# Blueberry_Pi.net
KiCad netlist of a schematic drawn in EAGLE
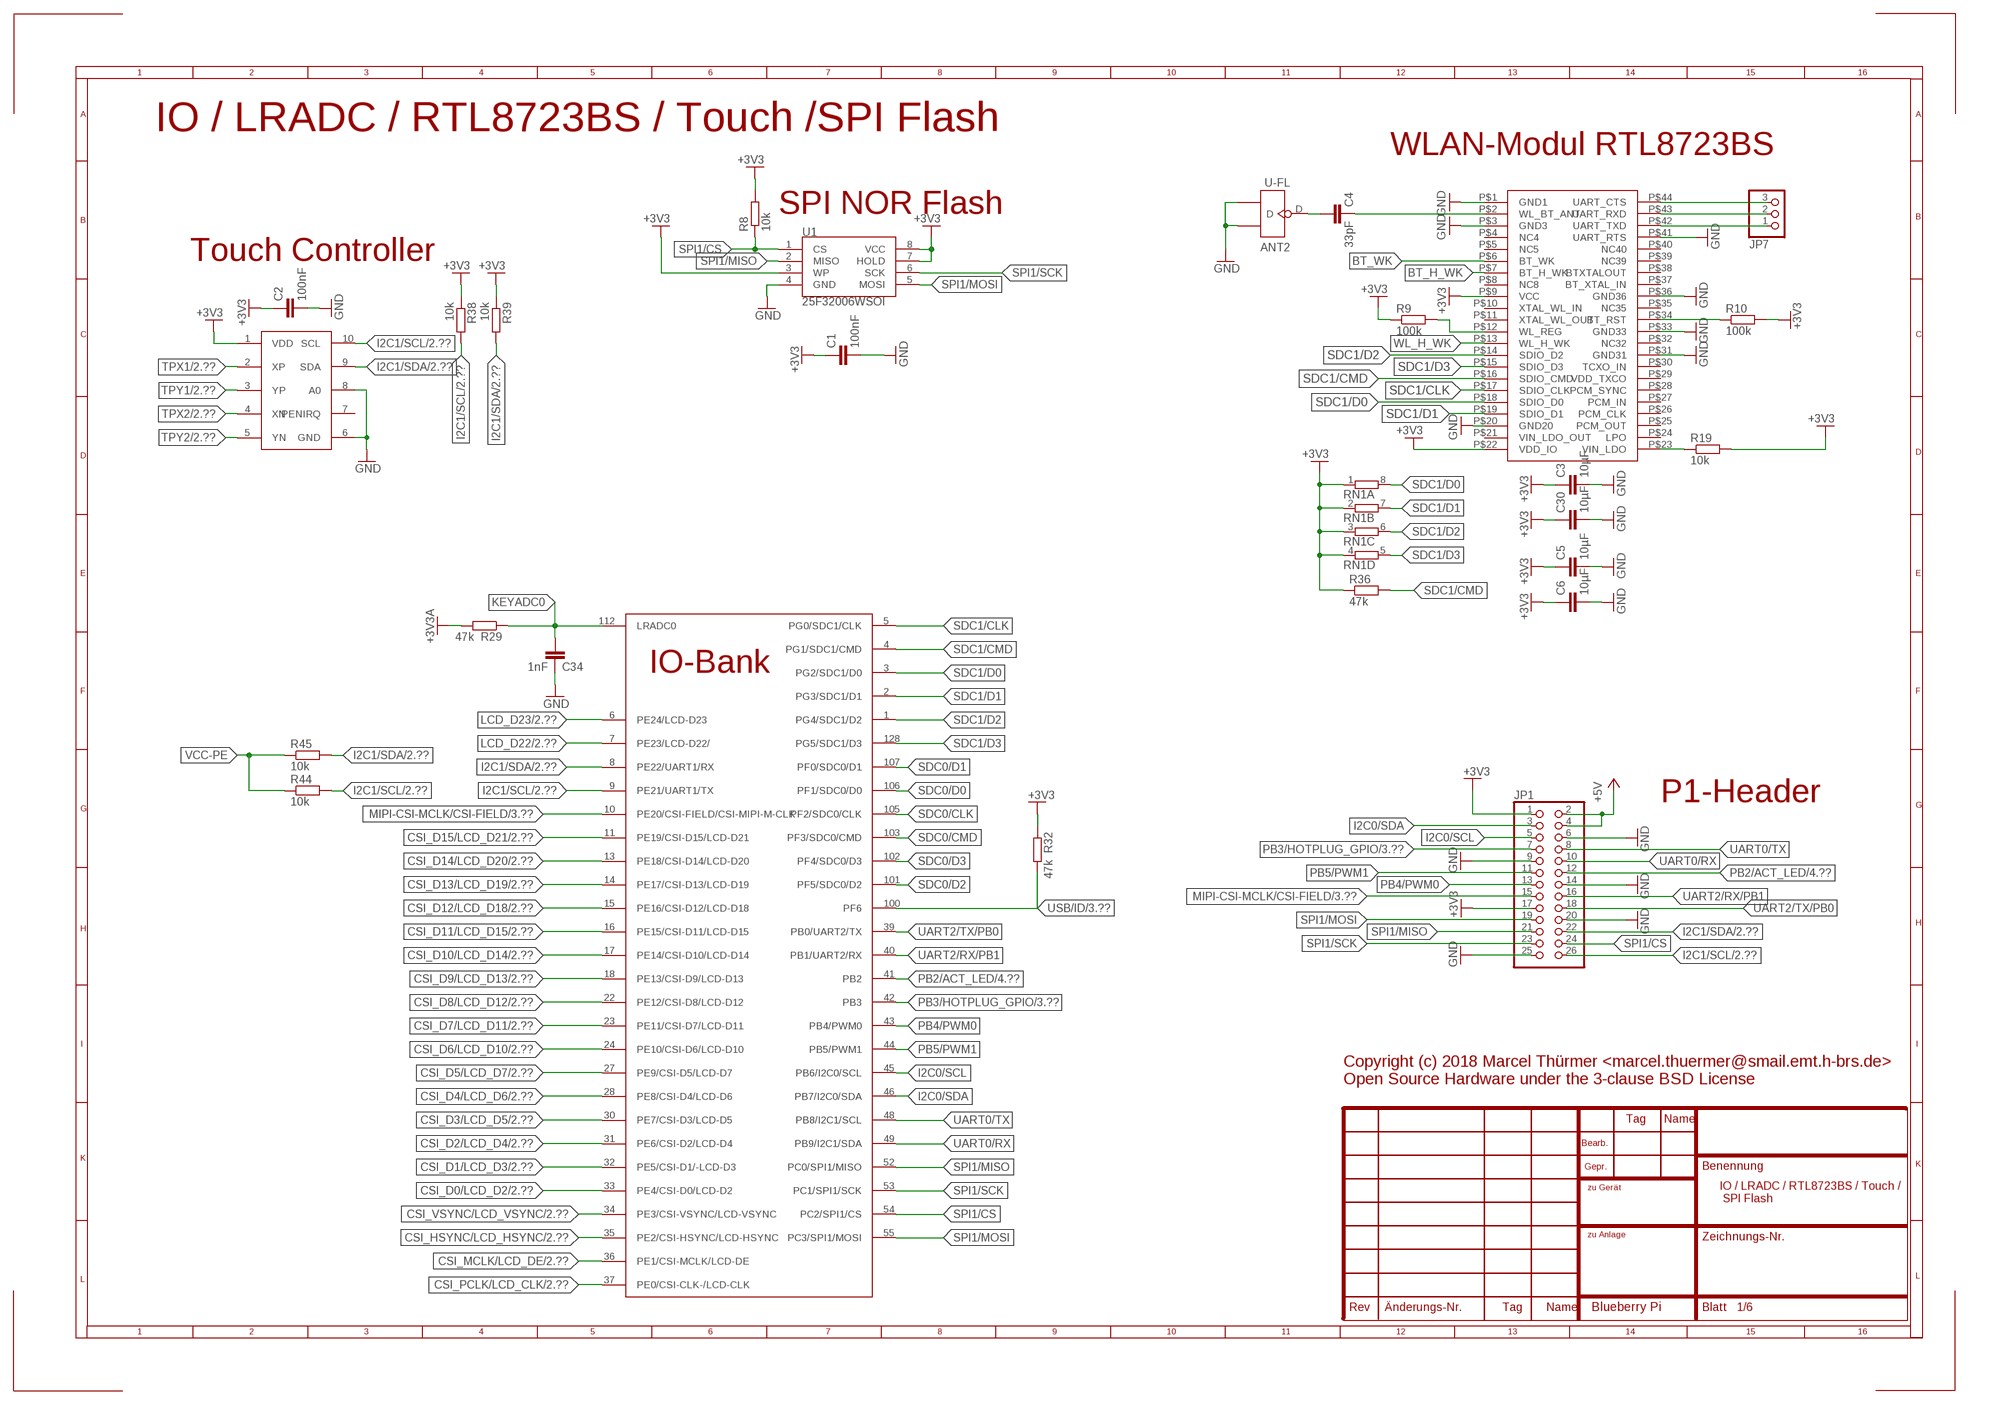
[diagram p0: schematic, sheet 1]
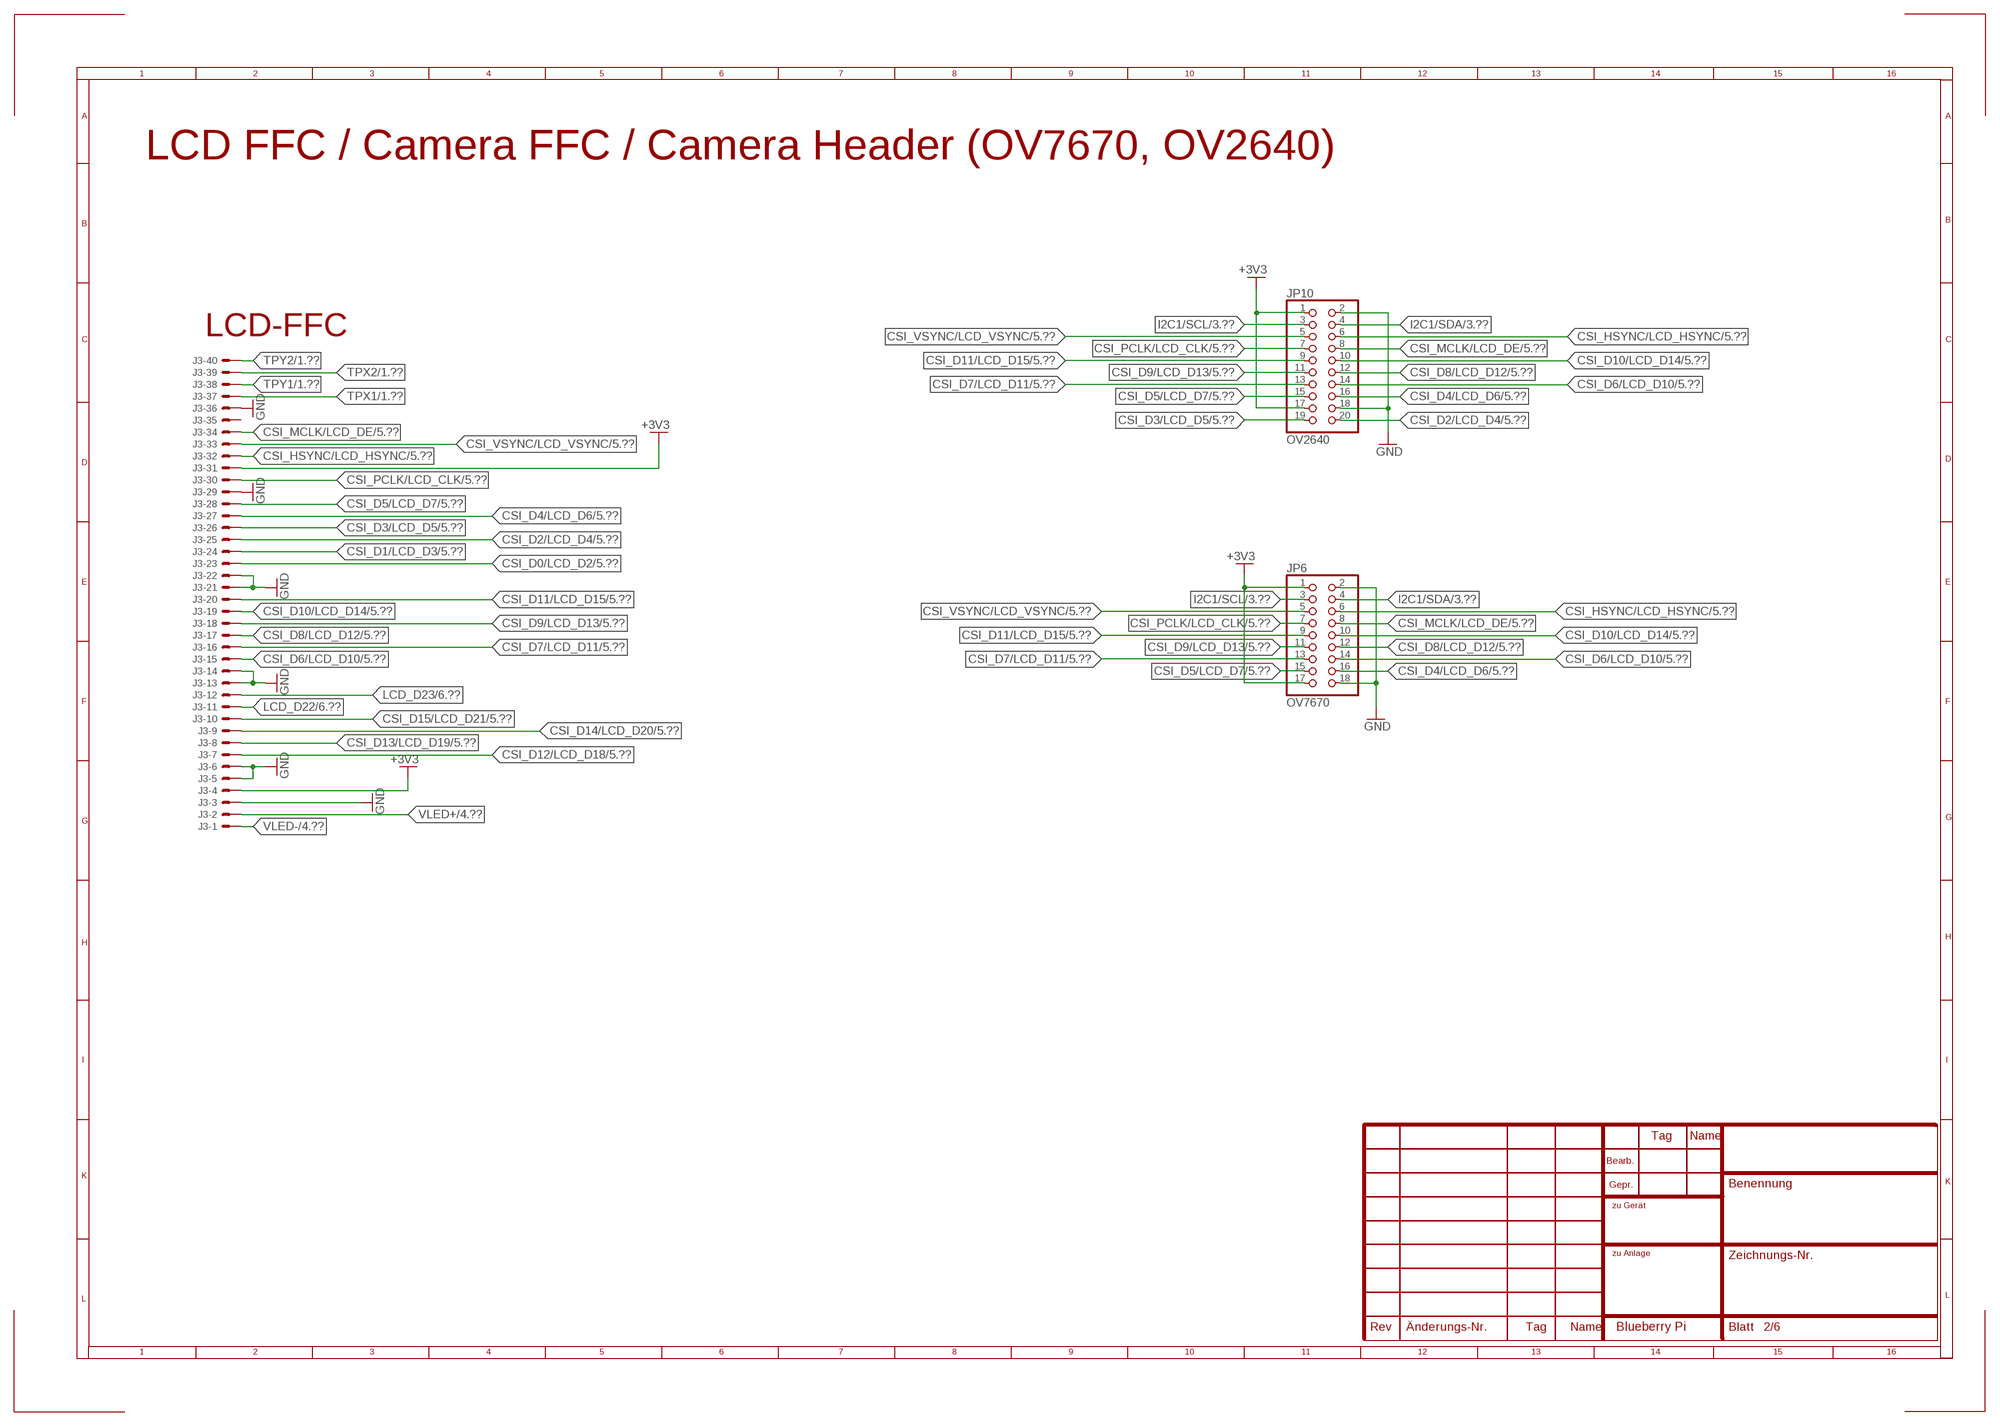
[diagram p1: schematic, sheet 2]
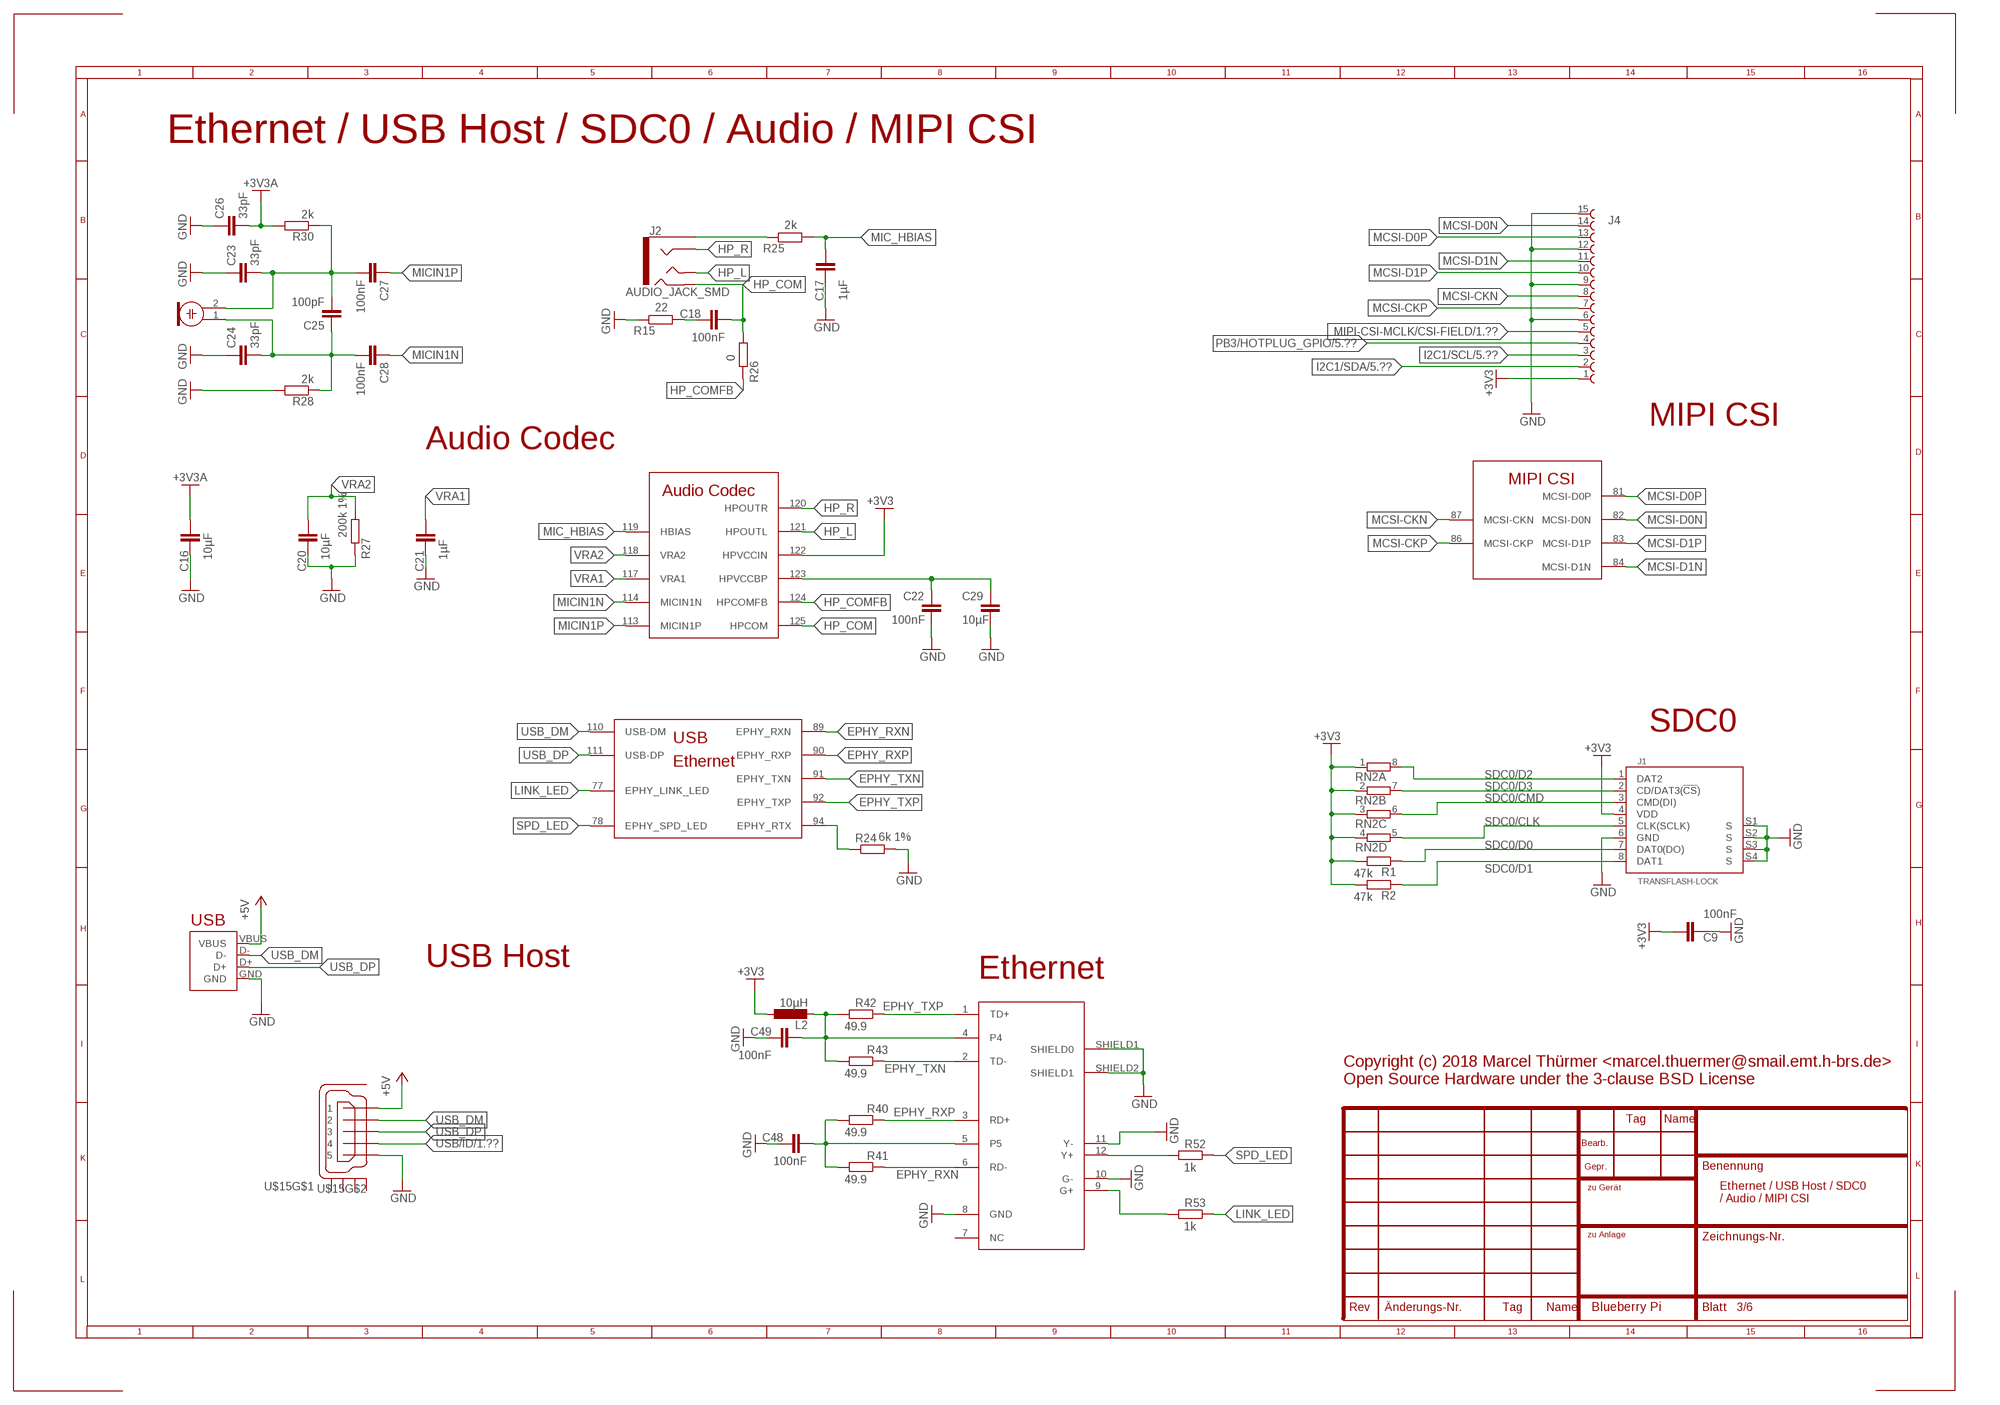
[diagram p2: schematic, sheet 3]
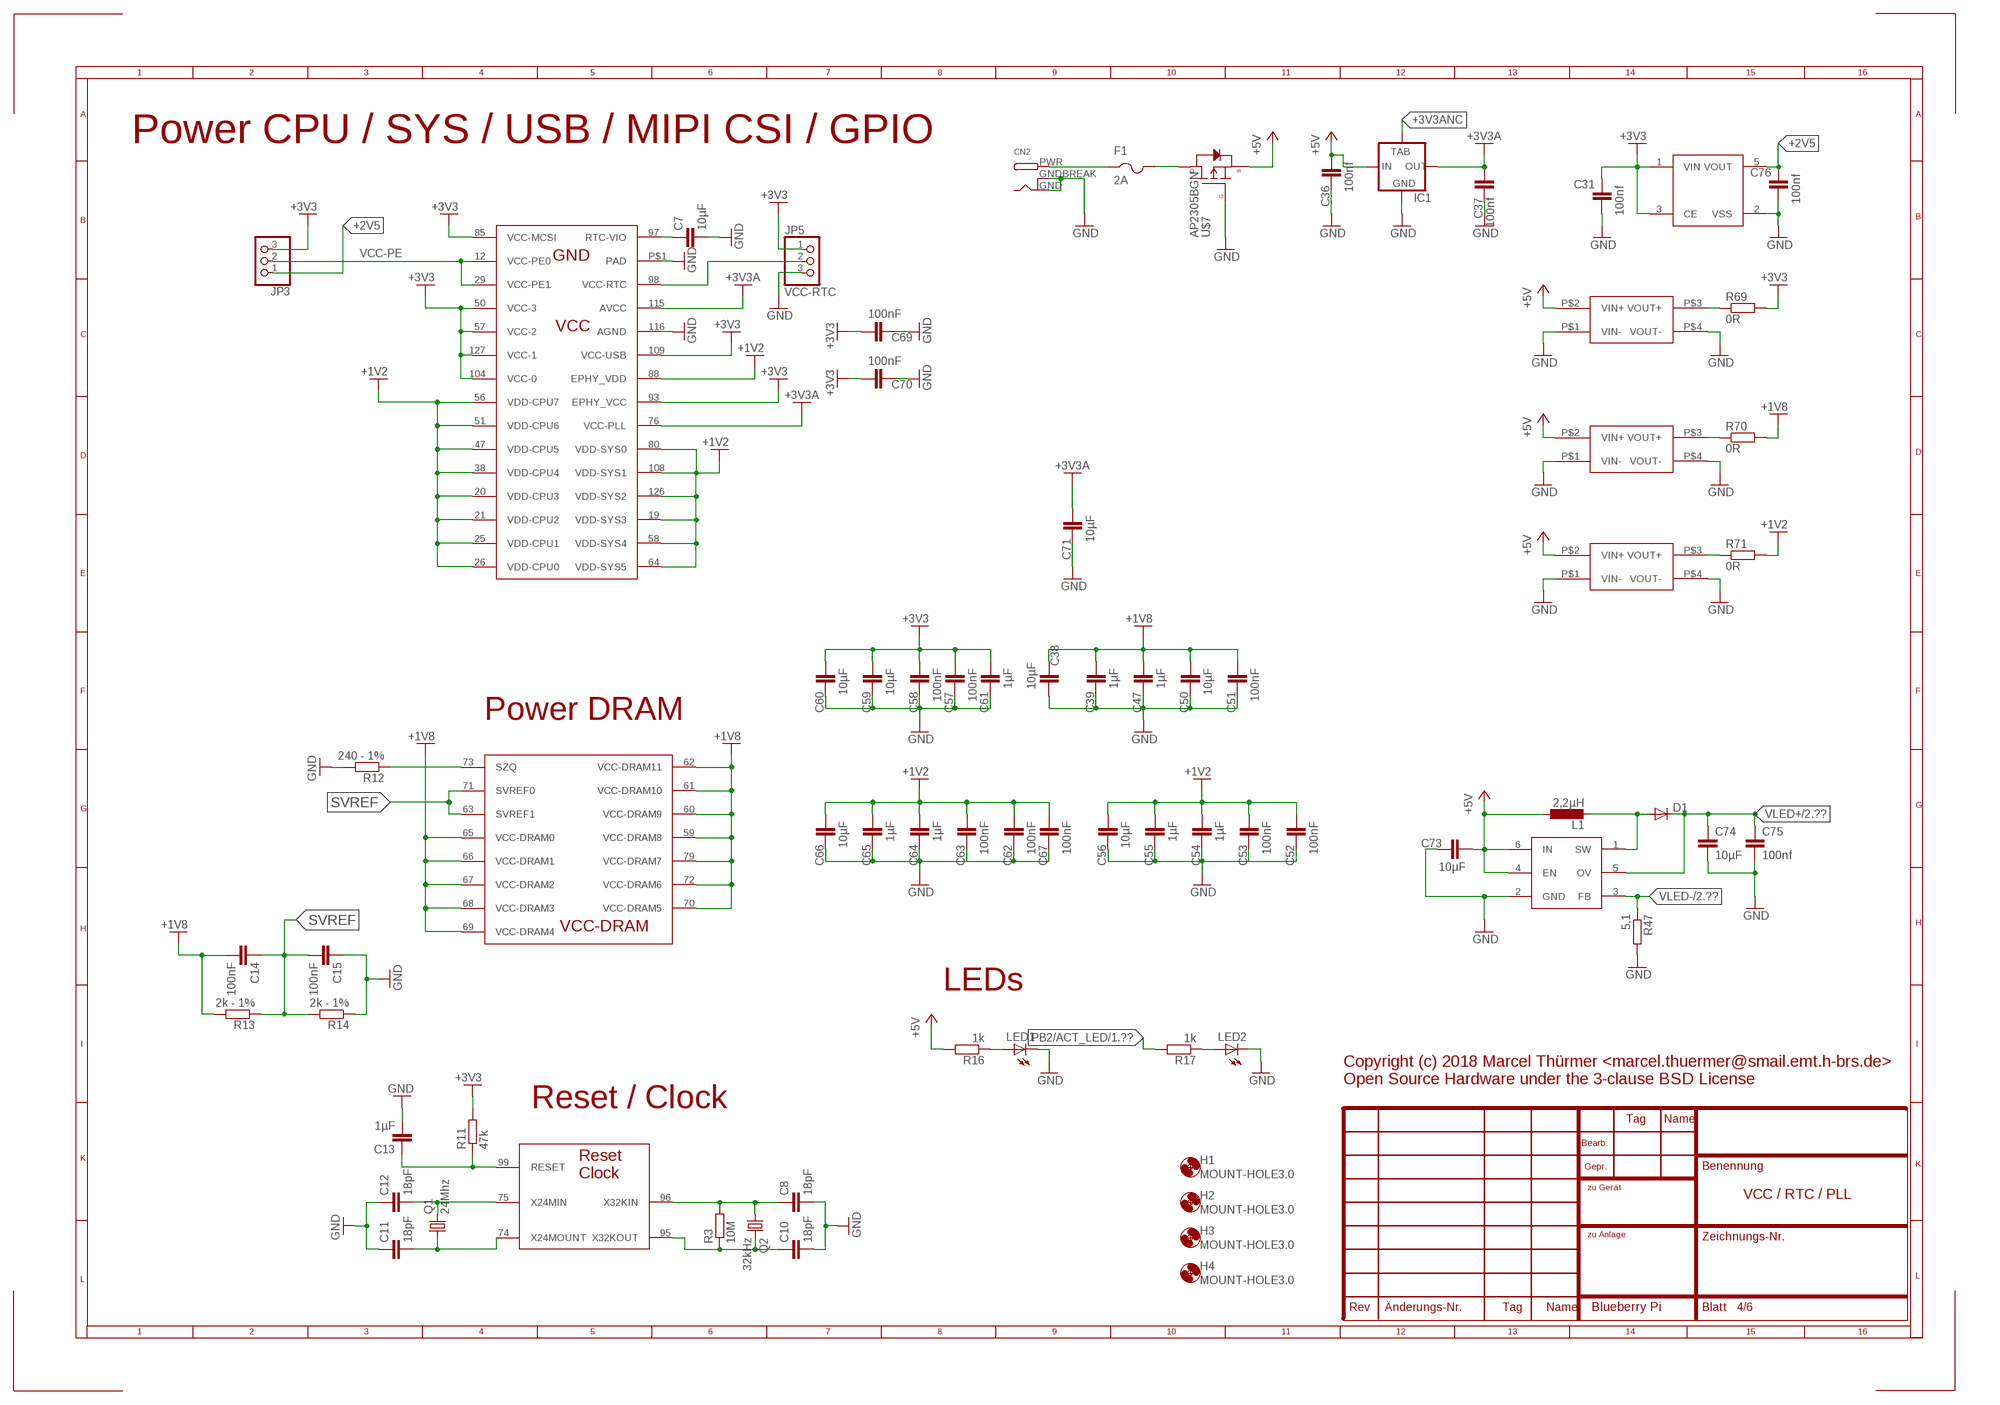
[diagram p3: schematic, sheet 4]
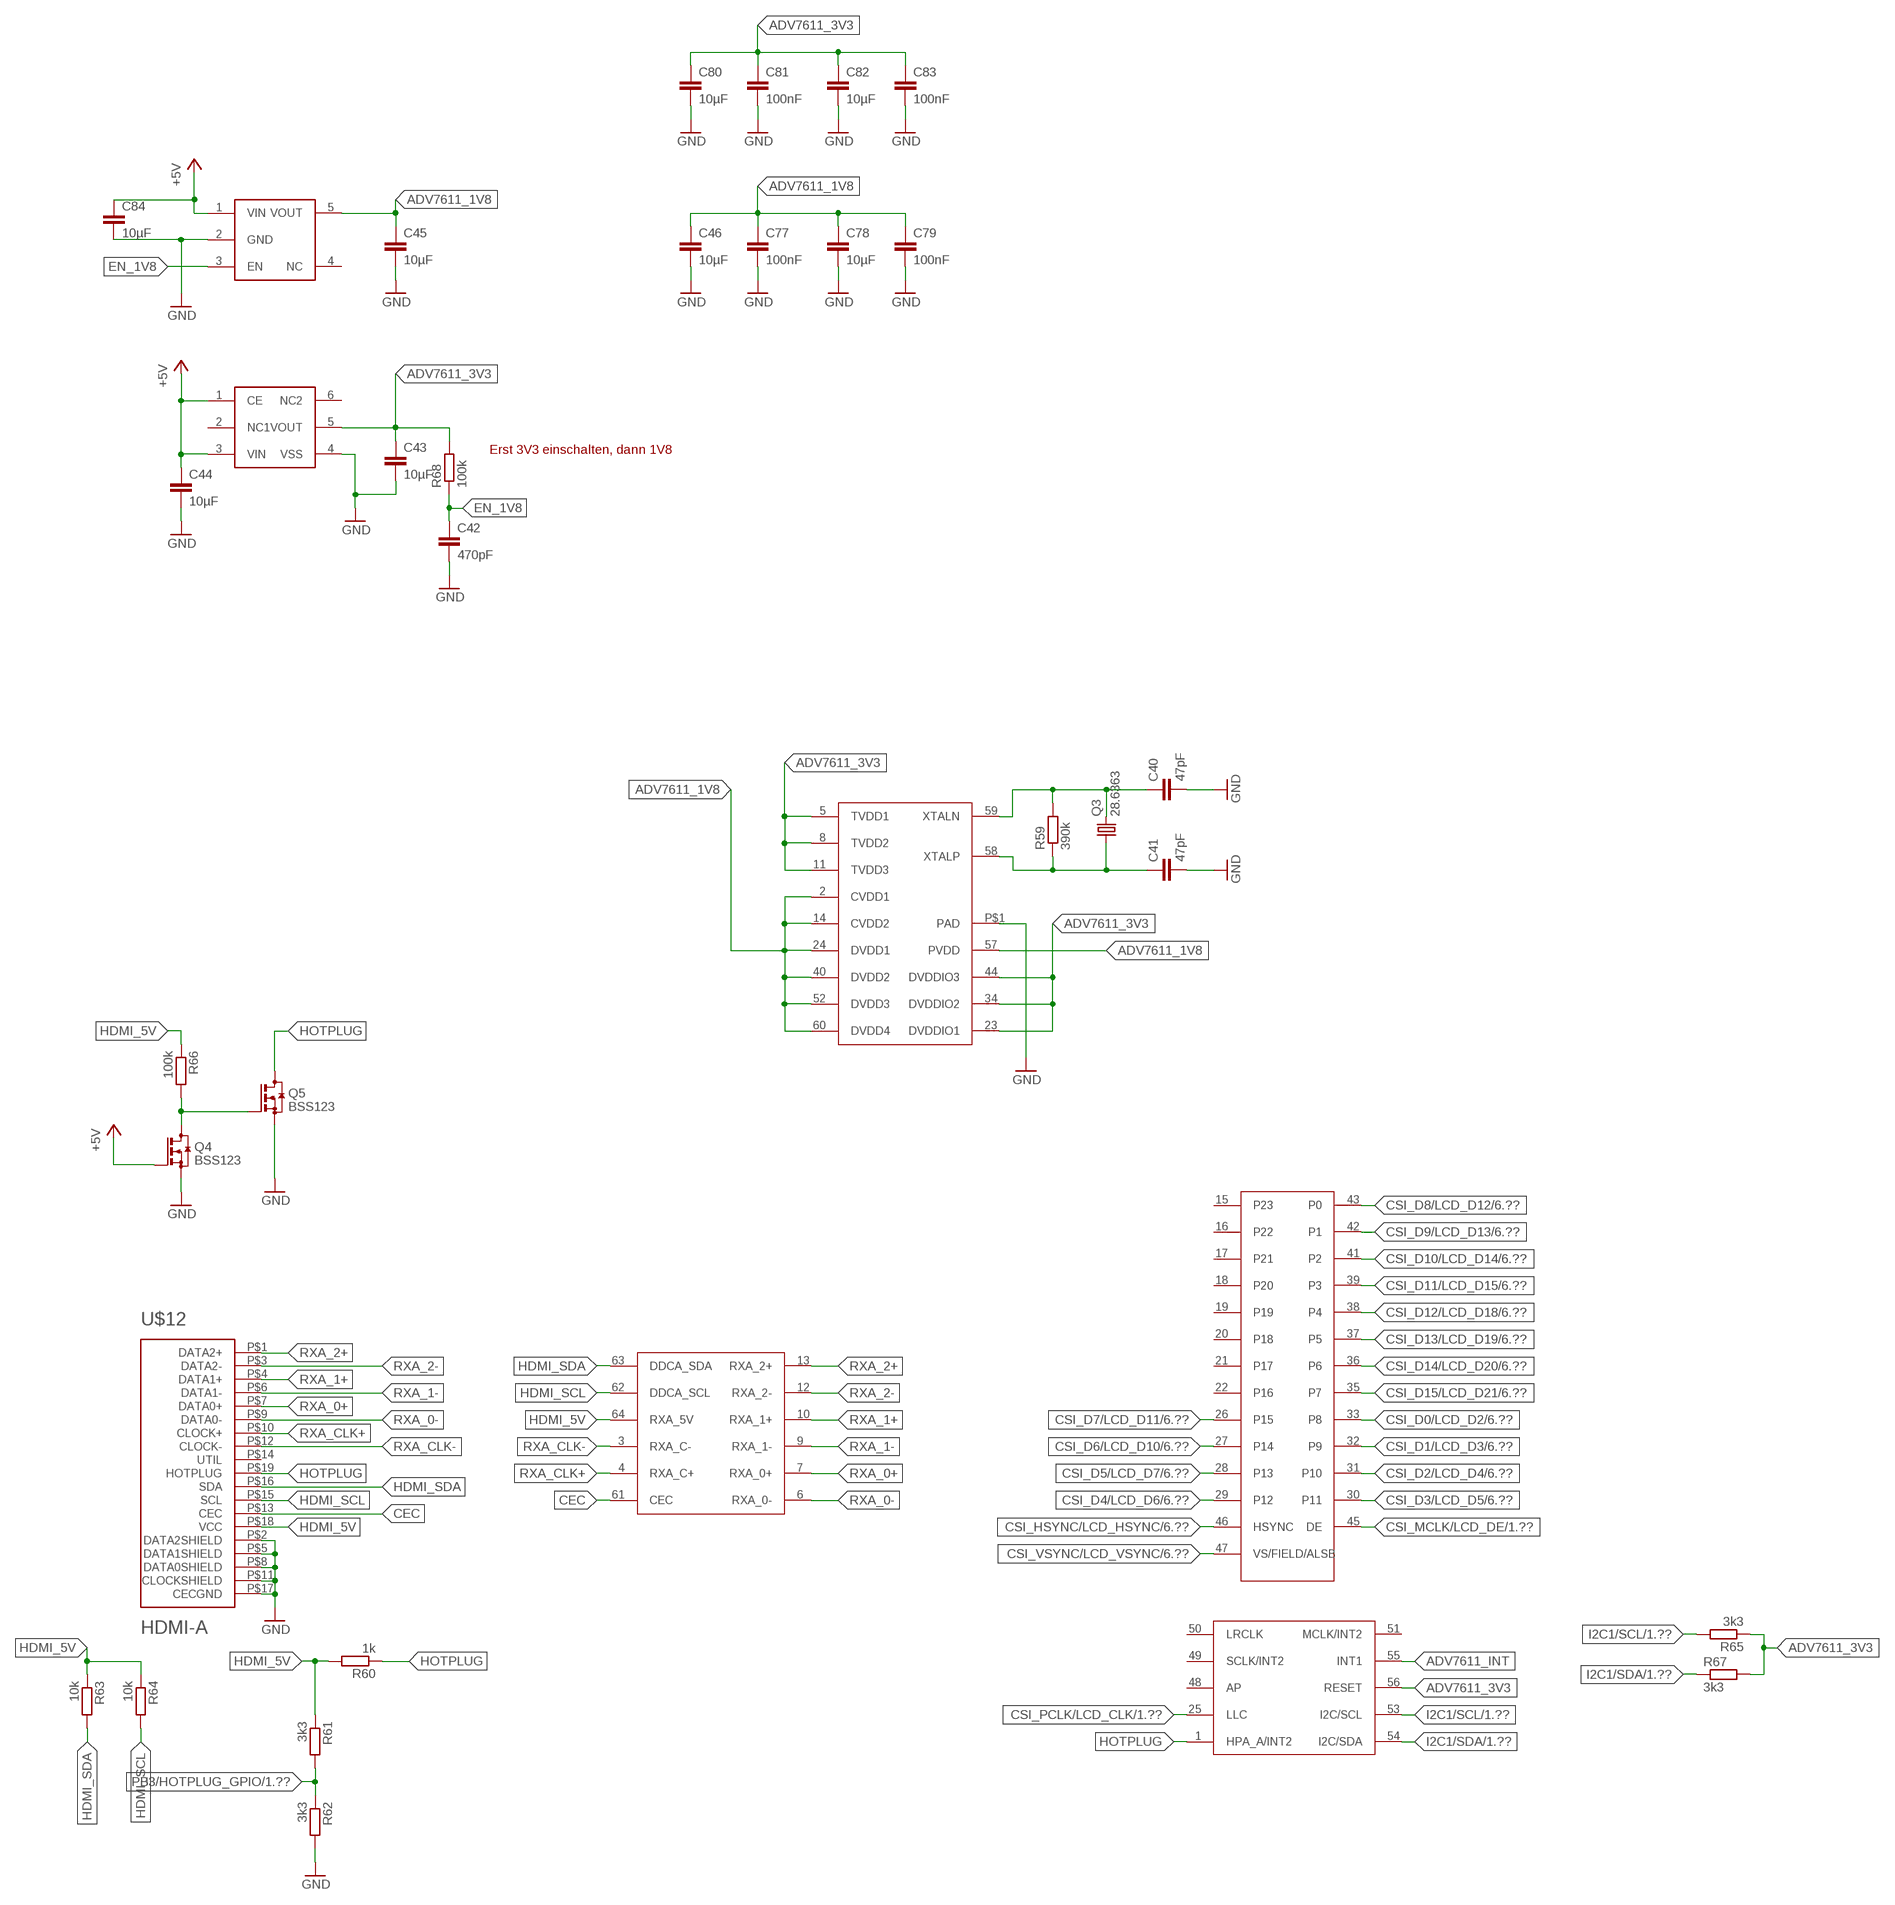
[diagram p4: schematic, sheet 5]
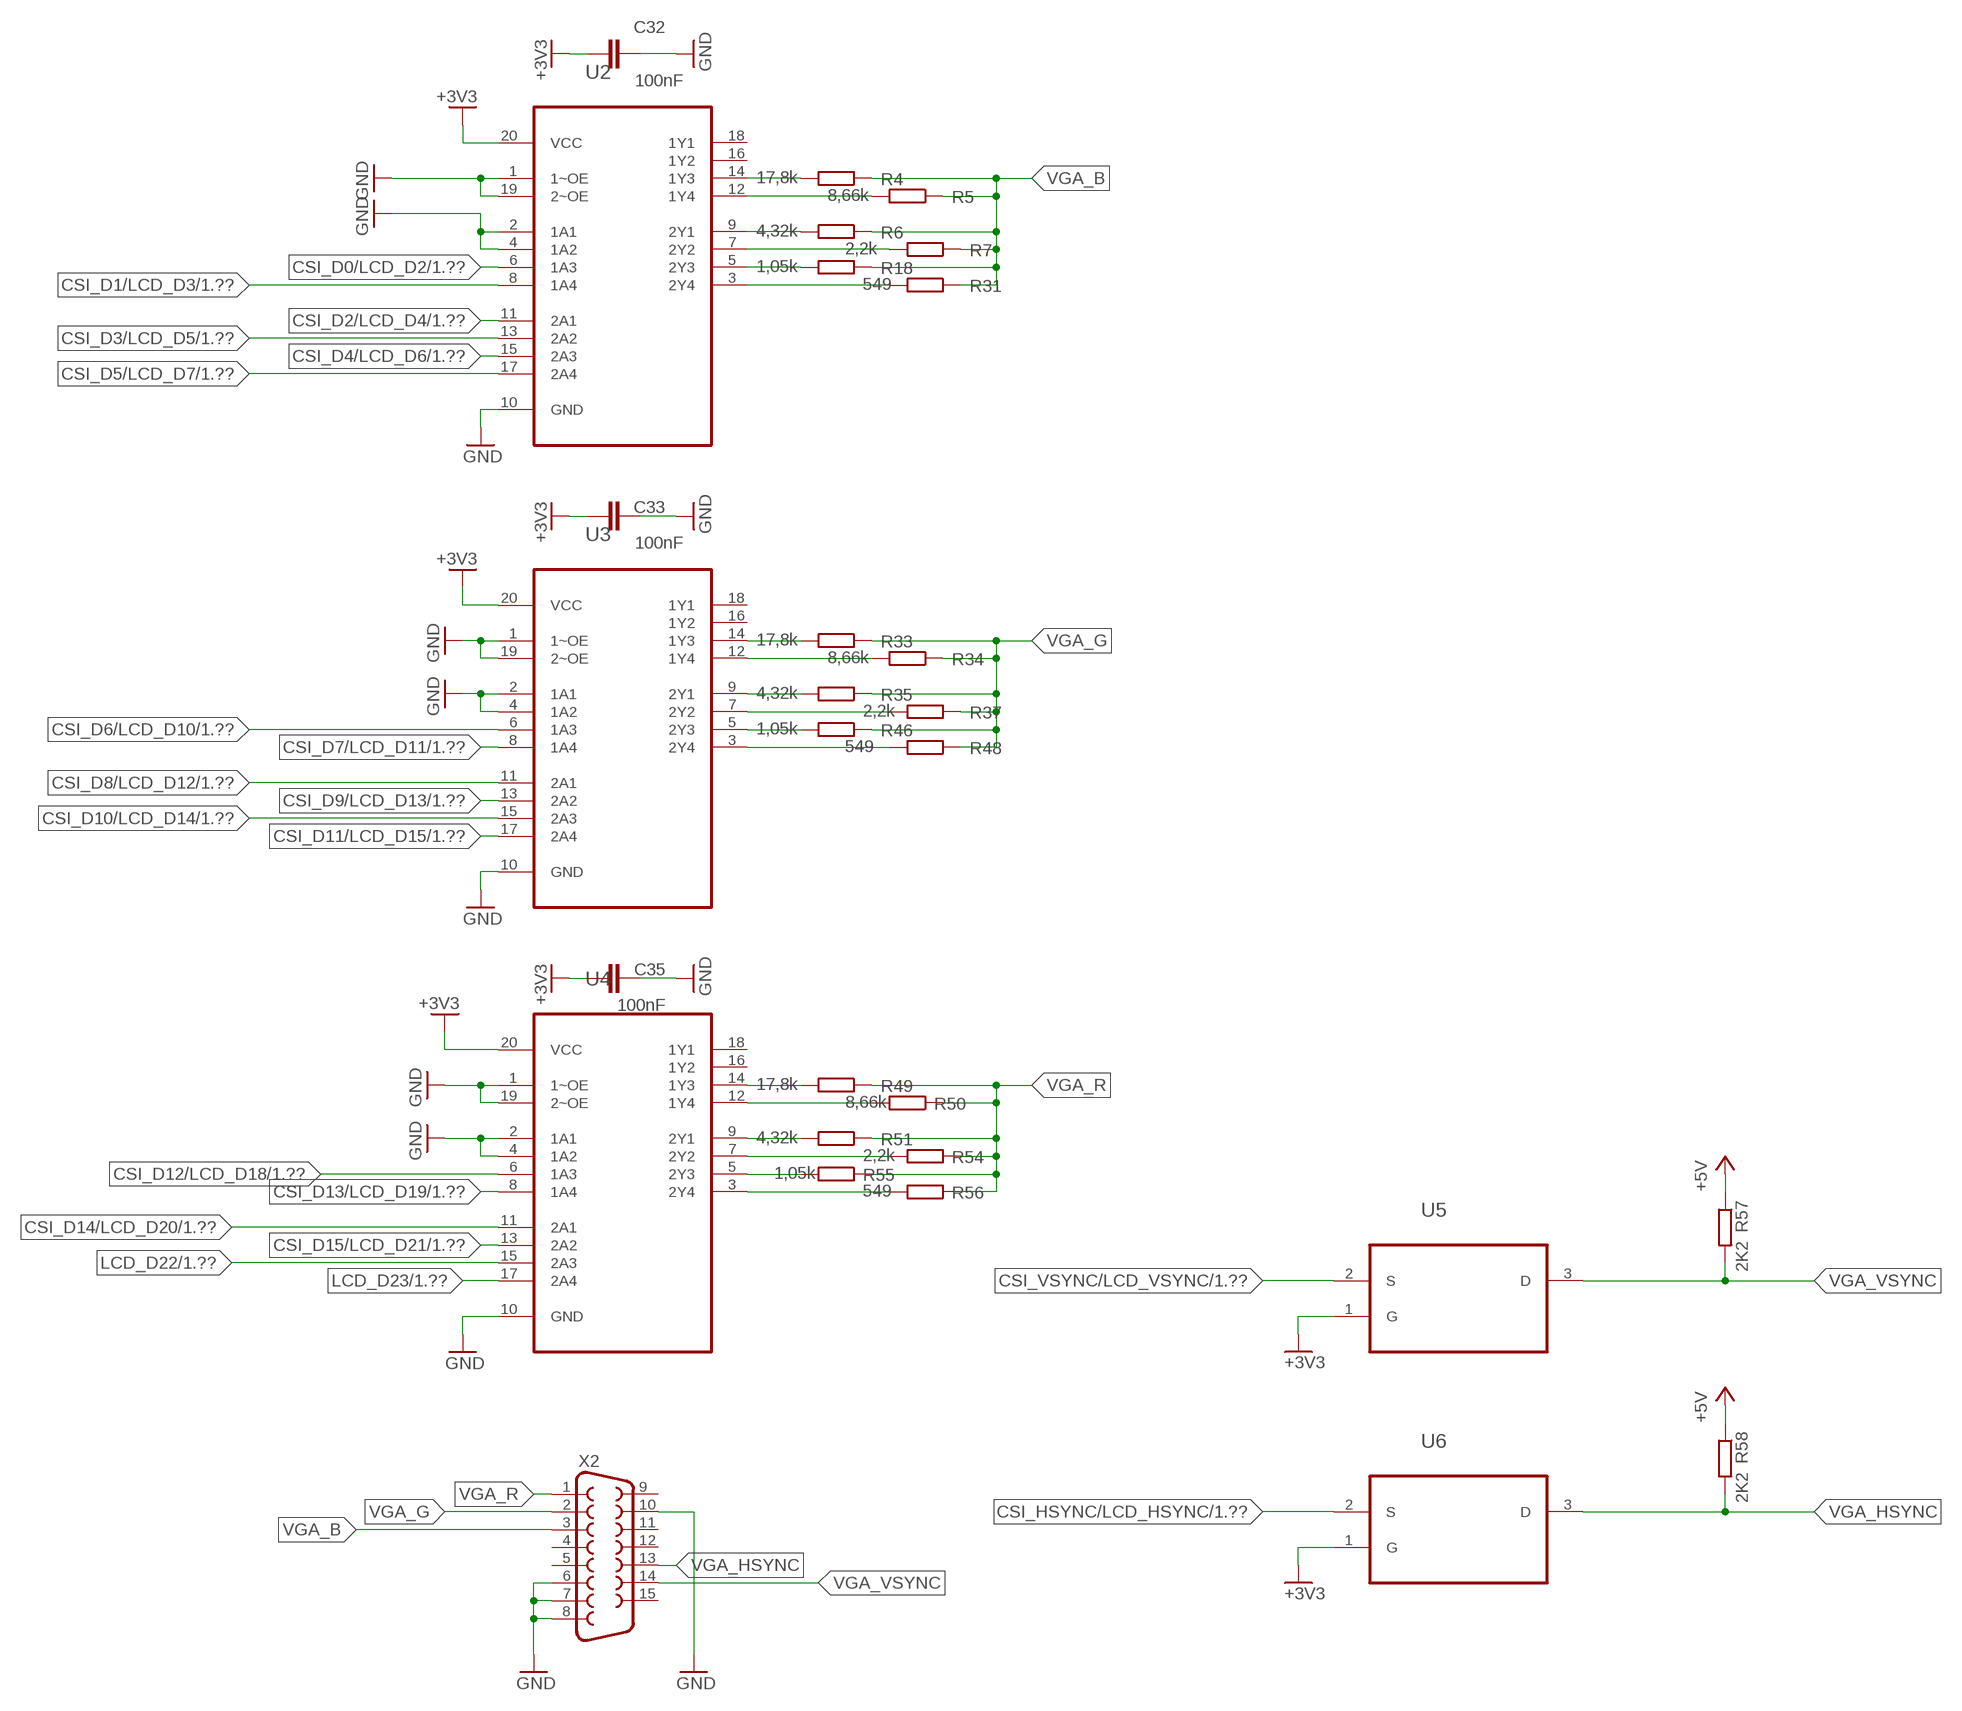
[diagram p5: schematic, sheet 6]

(export (version "E")
  (design (tool "Eeschema 10.0.6"))
  (components
    (comp (ref "C7")
      (value "10µF")
      (footprint "eagle-import:C0805")
      (libsource (lib "eagle-import") (part "C-EUC0805"))
    )
    (comp (ref "C8")
      (value "18pF")
      (footprint "eagle-import:C0603")
      (libsource (lib "eagle-import") (part "C-EUC0603"))
    )
    (comp (ref "C10")
      (value "18pF")
      (footprint "eagle-import:C0603")
      (libsource (lib "eagle-import") (part "C-EUC0603"))
    )
    (comp (ref "C11")
      (value "18pF")
      (footprint "eagle-import:C0603")
      (libsource (lib "eagle-import") (part "C-EUC0603"))
    )
    (comp (ref "C12")
      (value "18pF")
      (footprint "eagle-import:C0603")
      (libsource (lib "eagle-import") (part "C-EUC0603"))
    )
    (comp (ref "C13")
      (value "1µF")
      (footprint "eagle-import:C0603")
      (libsource (lib "eagle-import") (part "C-EUC0603"))
    )
    (comp (ref "C14")
      (value "100nF")
      (footprint "eagle-import:C0603")
      (libsource (lib "eagle-import") (part "C-EUC0603"))
    )
    (comp (ref "C15")
      (value "100nF")
      (footprint "eagle-import:C0603")
      (libsource (lib "eagle-import") (part "C-EUC0603"))
    )
    (comp (ref "C31")
      (value "100nf")
      (footprint "eagle-import:C0603")
      (libsource (lib "eagle-import") (part "C-EUC0603"))
    )
    (comp (ref "C36")
      (value "100nf")
      (footprint "eagle-import:C0603")
      (libsource (lib "eagle-import") (part "C-EUC0603"))
    )
    (comp (ref "C37")
      (value "100nf")
      (footprint "eagle-import:C0603")
      (libsource (lib "eagle-import") (part "C-EUC0603"))
    )
    (comp (ref "C38")
      (value "10µF")
      (footprint "eagle-import:C0603")
      (libsource (lib "eagle-import") (part "C-EUC0603"))
    )
    (comp (ref "C39")
      (value "1µF")
      (footprint "eagle-import:C0603")
      (libsource (lib "eagle-import") (part "C-EUC0603"))
    )
    (comp (ref "C47")
      (value "1µF")
      (footprint "eagle-import:C0603")
      (libsource (lib "eagle-import") (part "C-EUC0603"))
    )
    (comp (ref "C50")
      (value "10µF")
      (footprint "eagle-import:C0805")
      (libsource (lib "eagle-import") (part "C-EUC0805"))
    )
    (comp (ref "C51")
      (value "100nF")
      (footprint "eagle-import:C0603")
      (libsource (lib "eagle-import") (part "C-EUC0603"))
    )
    (comp (ref "C52")
      (value "100nF")
      (footprint "eagle-import:C0805")
      (libsource (lib "eagle-import") (part "C-EUC0805"))
    )
    (comp (ref "C53")
      (value "100nF")
      (footprint "eagle-import:C0603")
      (libsource (lib "eagle-import") (part "C-EUC0603"))
    )
    (comp (ref "C54")
      (value "1µF")
      (footprint "eagle-import:C0805")
      (libsource (lib "eagle-import") (part "C-EUC0805"))
    )
    (comp (ref "C55")
      (value "1µF")
      (footprint "eagle-import:C0603")
      (libsource (lib "eagle-import") (part "C-EUC0603"))
    )
    (comp (ref "C56")
      (value "10µF")
      (footprint "eagle-import:C0603")
      (libsource (lib "eagle-import") (part "C-EUC0603"))
    )
    (comp (ref "C57")
      (value "100nF")
      (footprint "eagle-import:C0603")
      (libsource (lib "eagle-import") (part "C-EUC0603"))
    )
    (comp (ref "C58")
      (value "100nF")
      (footprint "eagle-import:C0603")
      (libsource (lib "eagle-import") (part "C-EUC0603"))
    )
    (comp (ref "C59")
      (value "10µF")
      (footprint "eagle-import:C0805")
      (libsource (lib "eagle-import") (part "C-EUC0805"))
    )
    (comp (ref "C60")
      (value "10µF")
      (footprint "eagle-import:C0603")
      (libsource (lib "eagle-import") (part "C-EUC0603"))
    )
    (comp (ref "C61")
      (value "1µF")
      (footprint "eagle-import:C0805")
      (libsource (lib "eagle-import") (part "C-EUC0805"))
    )
    (comp (ref "C62")
      (value "100nF")
      (footprint "eagle-import:C0603")
      (libsource (lib "eagle-import") (part "C-EUC0603"))
    )
    (comp (ref "C63")
      (value "100nF")
      (footprint "eagle-import:C0805")
      (libsource (lib "eagle-import") (part "C-EUC0805"))
    )
    (comp (ref "C64")
      (value "1µF")
      (footprint "eagle-import:C0603")
      (libsource (lib "eagle-import") (part "C-EUC0603"))
    )
    (comp (ref "C65")
      (value "1µF")
      (footprint "eagle-import:C0603")
      (libsource (lib "eagle-import") (part "C-EUC0603"))
    )
    (comp (ref "C66")
      (value "10µF")
      (footprint "eagle-import:C0805")
      (libsource (lib "eagle-import") (part "C-EUC0805"))
    )
    (comp (ref "C67")
      (value "100nF")
      (footprint "eagle-import:C0603")
      (libsource (lib "eagle-import") (part "C-EUC0603"))
    )
    (comp (ref "C69")
      (value "100nF")
      (footprint "eagle-import:C0805")
      (libsource (lib "eagle-import") (part "C-EUC0805"))
    )
    (comp (ref "C70")
      (value "100nF")
      (footprint "eagle-import:C0603")
      (libsource (lib "eagle-import") (part "C-EUC0603"))
    )
    (comp (ref "C71")
      (value "10µF")
      (footprint "eagle-import:C0603")
      (libsource (lib "eagle-import") (part "C-EUC0603"))
    )
    (comp (ref "C73")
      (value "10µF")
      (footprint "eagle-import:C0805")
      (libsource (lib "eagle-import") (part "C-EUC0805"))
    )
    (comp (ref "C74")
      (value "10µF")
      (footprint "eagle-import:C0805")
      (libsource (lib "eagle-import") (part "C-EUC0805"))
    )
    (comp (ref "C75")
      (value "100nf")
      (footprint "eagle-import:C0603")
      (libsource (lib "eagle-import") (part "C-EUC0603"))
    )
    (comp (ref "C76")
      (value "100nf")
      (footprint "eagle-import:C0603")
      (libsource (lib "eagle-import") (part "C-EUC0603"))
    )
    (comp (ref "CN2")
      (value "DCBARRELPTH")
      (footprint "eagle-import:DCJACK_2MM_PTH")
      (libsource (lib "eagle-import") (part "DCBARRELPTH"))
    )
    (comp (ref "D1")
      (value "DIODE-SOD323-W")
      (footprint "eagle-import:SOD323-W")
      (libsource (lib "eagle-import") (part "DIODE-SOD323-W"))
    )
    (comp (ref "F1")
      (value "2A")
      (footprint "eagle-import:R1206")
      (libsource (lib "eagle-import") (part "PTCFUSE-1206"))
    )
    (comp (ref "H1")
      (value "MOUNT-HOLE3.0")
      (footprint "eagle-import:3,0")
      (libsource (lib "eagle-import") (part "MOUNT-HOLE3.0"))
    )
    (comp (ref "H2")
      (value "MOUNT-HOLE3.0")
      (footprint "eagle-import:3,0")
      (libsource (lib "eagle-import") (part "MOUNT-HOLE3.0"))
    )
    (comp (ref "H3")
      (value "MOUNT-HOLE3.0")
      (footprint "eagle-import:3,0")
      (libsource (lib "eagle-import") (part "MOUNT-HOLE3.0"))
    )
    (comp (ref "H4")
      (value "MOUNT-HOLE3.0")
      (footprint "eagle-import:3,0")
      (libsource (lib "eagle-import") (part "MOUNT-HOLE3.0"))
    )
    (comp (ref "IC1")
      (value "LM1117")
      (footprint "eagle-import:SOT223")
      (libsource (lib "eagle-import") (part "LM1117"))
    )
    (comp (ref "JP3")
      (value "PINHD-1X3")
      (footprint "eagle-import:1X03")
      (libsource (lib "eagle-import") (part "PINHD-1X3"))
    )
    (comp (ref "JP5")
      (value "VCC-RTC")
      (footprint "eagle-import:1X03")
      (libsource (lib "eagle-import") (part "PINHD-1X3"))
    )
    (comp (ref "L1")
      (value "2,2µH")
      (footprint "eagle-import:ODD-INDUCTOR")
      (libsource (lib "eagle-import") (part "L-EU"))
    )
    (comp (ref "LED1")
      (value "LEDCHIPLED_0805")
      (footprint "eagle-import:CHIPLED_0805")
      (libsource (lib "eagle-import") (part "LEDCHIPLED_0805"))
    )
    (comp (ref "LED2")
      (value "LEDCHIPLED_0805")
      (footprint "eagle-import:CHIPLED_0805")
      (libsource (lib "eagle-import") (part "LEDCHIPLED_0805"))
    )
    (comp (ref "Q1")
      (value "24Mhz")
      (footprint "eagle-import:HC49U-V")
      (libsource (lib "eagle-import") (part "CRYSTALHC49U-V"))
    )
    (comp (ref "Q2")
      (value "32kHz")
      (footprint "eagle-import:TC38H")
      (libsource (lib "eagle-import") (part "CRYSTALTC38H"))
    )
    (comp (ref "R3")
      (value "10M")
      (footprint "eagle-import:R0603")
      (libsource (lib "eagle-import") (part "R-EU_R0603"))
    )
    (comp (ref "R11")
      (value "47k")
      (footprint "eagle-import:R0603")
      (libsource (lib "eagle-import") (part "R-EU_R0603"))
    )
    (comp (ref "R12")
      (value "240 - 1%")
      (footprint "eagle-import:R0603")
      (libsource (lib "eagle-import") (part "R-EU_R0603"))
    )
    (comp (ref "R13")
      (value "2k - 1%")
      (footprint "eagle-import:R0603")
      (libsource (lib "eagle-import") (part "R-EU_R0603"))
    )
    (comp (ref "R14")
      (value "2k - 1%")
      (footprint "eagle-import:R0603")
      (libsource (lib "eagle-import") (part "R-EU_R0603"))
    )
    (comp (ref "R16")
      (value "1k")
      (footprint "eagle-import:R0603")
      (libsource (lib "eagle-import") (part "R-EU_R0603"))
    )
    (comp (ref "R17")
      (value "1k")
      (footprint "eagle-import:R0603")
      (libsource (lib "eagle-import") (part "R-EU_R0603"))
    )
    (comp (ref "R47")
      (value "5,1")
      (footprint "eagle-import:R0603")
      (libsource (lib "eagle-import") (part "R-EU_R0603"))
    )
    (comp (ref "R69")
      (value "0R")
      (footprint "eagle-import:R0603")
      (libsource (lib "eagle-import") (part "R-EU_R0603"))
    )
    (comp (ref "R70")
      (value "0R")
      (footprint "eagle-import:R0603")
      (libsource (lib "eagle-import") (part "R-EU_R0603"))
    )
    (comp (ref "R71")
      (value "0R")
      (footprint "eagle-import:R0603")
      (libsource (lib "eagle-import") (part "R-EU_R0603"))
    )
    (comp (ref "U$1")
      (value "V3S")
      (footprint "eagle-import:QFP-128")
      (libsource (lib "eagle-import") (part "V3S"))
    )
    (comp (ref "U$4")
      (value "MP1584-MINI")
      (footprint "eagle-import:MINI-DC-BRICK")
      (libsource (lib "eagle-import") (part "MP1584-MINI"))
    )
    (comp (ref "U$6")
      (value "XC6204")
      (footprint "eagle-import:SOT25")
      (libsource (lib "eagle-import") (part "XC6204XC6204"))
    )
    (comp (ref "U$7")
      (value "AP2305BGN")
      (footprint "eagle-import:SOT23-3")
      (libsource (lib "eagle-import") (part "P-CHANNEL-MOSFET"))
    )
    (comp (ref "U$9")
      (value "PT4101")
      (footprint "eagle-import:SOT23-6")
      (libsource (lib "eagle-import") (part "PT4101"))
    )
    (comp (ref "U$10")
      (value "MP1584-MINI")
      (footprint "eagle-import:MINI-DC-BRICK")
      (libsource (lib "eagle-import") (part "MP1584-MINI"))
    )
    (comp (ref "U$11")
      (value "MP1584-MINI")
      (footprint "eagle-import:MINI-DC-BRICK")
      (libsource (lib "eagle-import") (part "MP1584-MINI"))
    )
    (comp (ref "C9")
      (value "100nF")
      (footprint "eagle-import:C0603")
      (libsource (lib "eagle-import") (part "C-EUC0603"))
    )
    (comp (ref "C16")
      (value "10µF")
      (footprint "eagle-import:C0805")
      (libsource (lib "eagle-import") (part "C-EUC0805"))
    )
    (comp (ref "C17")
      (value "1µF")
      (footprint "eagle-import:C0603")
      (libsource (lib "eagle-import") (part "C-EUC0603"))
    )
    (comp (ref "C18")
      (value "100nF")
      (footprint "eagle-import:C0603")
      (libsource (lib "eagle-import") (part "C-EUC0603"))
    )
    (comp (ref "C20")
      (value "10µF")
      (footprint "eagle-import:C0805")
      (libsource (lib "eagle-import") (part "C-EUC0805"))
    )
    (comp (ref "C21")
      (value "1µF")
      (footprint "eagle-import:C0603")
      (libsource (lib "eagle-import") (part "C-EUC0603"))
    )
    (comp (ref "C22")
      (value "100nF")
      (footprint "eagle-import:C0603")
      (libsource (lib "eagle-import") (part "C-EUC0603"))
    )
    (comp (ref "C23")
      (value "33pF")
      (footprint "eagle-import:C0603")
      (libsource (lib "eagle-import") (part "C-EUC0603"))
    )
    (comp (ref "C24")
      (value "33pF")
      (footprint "eagle-import:C0603")
      (libsource (lib "eagle-import") (part "C-EUC0603"))
    )
    (comp (ref "C25")
      (value "100pF")
      (footprint "eagle-import:C0603")
      (libsource (lib "eagle-import") (part "C-EUC0603"))
    )
    (comp (ref "C26")
      (value "33pF")
      (footprint "eagle-import:C0603")
      (libsource (lib "eagle-import") (part "C-EUC0603"))
    )
    (comp (ref "C27")
      (value "100nF")
      (footprint "eagle-import:C0603")
      (libsource (lib "eagle-import") (part "C-EUC0603"))
    )
    (comp (ref "C28")
      (value "100nF")
      (footprint "eagle-import:C0603")
      (libsource (lib "eagle-import") (part "C-EUC0603"))
    )
    (comp (ref "C29")
      (value "10µF")
      (footprint "eagle-import:C0805")
      (libsource (lib "eagle-import") (part "C-EUC0805"))
    )
    (comp (ref "C48")
      (value "100nF")
      (footprint "eagle-import:C0603")
      (libsource (lib "eagle-import") (part "C-EUC0603"))
    )
    (comp (ref "C49")
      (value "100nF")
      (footprint "eagle-import:C0603")
      (libsource (lib "eagle-import") (part "C-EUC0603"))
    )
    (comp (ref "J1")
      (value "TRANSFLASH-LOCK")
      (footprint "eagle-import:TRANSFLASH-LOCK-SOCK")
      (libsource (lib "eagle-import") (part "TRANSFLASH-LOCK"))
    )
    (comp (ref "J2")
      (value "AUDIO_JACK_SMD")
      (footprint "eagle-import:AUDIO_JACK_3.5MM_TRRS_SMD_RA")
      (libsource (lib "eagle-import") (part "AUDIO_JACK_TRRSSMD_RA"))
    )
    (comp (ref "J4")
      (value "68611514122")
      (footprint "eagle-import:68611514122")
      (libsource (lib "eagle-import") (part "68611514122"))
    )
    (comp (ref "L2")
      (value "10µH")
      (footprint "eagle-import:L0805")
      (libsource (lib "eagle-import") (part "L-EUL0805"))
    )
    (comp (ref "MIC")
      (value "ELECTRET_MICROPHON-F6035AP")
      (footprint "eagle-import:F6035AP")
      (libsource (lib "eagle-import") (part "ELECTRET_MICROPHON-F6035AP"))
    )
    (comp (ref "R1")
      (value "47k")
      (footprint "eagle-import:R0603")
      (libsource (lib "eagle-import") (part "R-EU_R0603"))
    )
    (comp (ref "R2")
      (value "47k")
      (footprint "eagle-import:R0603")
      (libsource (lib "eagle-import") (part "R-EU_R0603"))
    )
    (comp (ref "R15")
      (value "22")
      (footprint "eagle-import:R0603")
      (libsource (lib "eagle-import") (part "R-EU_R0603"))
    )
    (comp (ref "R24")
      (value "6k 1%")
      (footprint "eagle-import:R0603")
      (libsource (lib "eagle-import") (part "R-EU_R0603"))
    )
    (comp (ref "R25")
      (value "2k")
      (footprint "eagle-import:R0603")
      (libsource (lib "eagle-import") (part "R-EU_R0603"))
    )
    (comp (ref "R26")
      (value "0")
      (footprint "eagle-import:R0603")
      (libsource (lib "eagle-import") (part "R-EU_R0603"))
    )
    (comp (ref "R27")
      (value "200k 1%")
      (footprint "eagle-import:R0603")
      (libsource (lib "eagle-import") (part "R-EU_R0603"))
    )
    (comp (ref "R28")
      (value "2k")
      (footprint "eagle-import:R0603")
      (libsource (lib "eagle-import") (part "R-EU_R0603"))
    )
    (comp (ref "R30")
      (value "2k")
      (footprint "eagle-import:R0603")
      (libsource (lib "eagle-import") (part "R-EU_R0603"))
    )
    (comp (ref "R40")
      (value "49.9")
      (footprint "eagle-import:R0603")
      (libsource (lib "eagle-import") (part "R-EU_R0603"))
    )
    (comp (ref "R41")
      (value "49.9")
      (footprint "eagle-import:R0603")
      (libsource (lib "eagle-import") (part "R-EU_R0603"))
    )
    (comp (ref "R42")
      (value "49.9")
      (footprint "eagle-import:R0603")
      (libsource (lib "eagle-import") (part "R-EU_R0603"))
    )
    (comp (ref "R43")
      (value "49.9")
      (footprint "eagle-import:R0603")
      (libsource (lib "eagle-import") (part "R-EU_R0603"))
    )
    (comp (ref "R52")
      (value "1k")
      (footprint "eagle-import:R0603")
      (libsource (lib "eagle-import") (part "R-EU_R0603"))
    )
    (comp (ref "R53")
      (value "1k")
      (footprint "eagle-import:R0603")
      (libsource (lib "eagle-import") (part "R-EU_R0603"))
    )
    (comp (ref "RN2")
      (value "4R-NEXB38V")
      (footprint "eagle-import:EXB38V")
      (libsource (lib "eagle-import") (part "4R-NEXB38V"))
    )
    (comp (ref "U$3")
      (value "HR911105A")
      (footprint "eagle-import:RJ45")
      (libsource (lib "eagle-import") (part "HR911105A"))
    )
    (comp (ref "U$15")
      (value "CON-HIROSE_MICRO-USB-SHIELD-ZX62R-B-5P")
      (footprint "eagle-import:CON-HIROSE_ZX62R-B-5P")
      (libsource (lib "eagle-import") (part "CON-HIROSE_MICRO-USB-SHIELD-ZX62R-B-5P"))
    )
    (comp (ref "X1")
      (value "USB-B-S")
      (footprint "eagle-import:USB-B-SMT")
      (libsource (lib "eagle-import") (part "USB-B-S"))
    )
    (comp (ref "ANT2")
      (value "U-FL")
      (footprint "eagle-import:U-FL3P-SMD-2.6X2.6X1.0MM")
      (libsource (lib "eagle-import") (part "ANTENNA-CONN-U-FL(3P)"))
    )
    (comp (ref "C1")
      (value "100nF")
      (footprint "eagle-import:C0603")
      (libsource (lib "eagle-import") (part "C-EUC0603"))
    )
    (comp (ref "C2")
      (value "100nF")
      (footprint "eagle-import:C0603")
      (libsource (lib "eagle-import") (part "C-EUC0603"))
    )
    (comp (ref "C3")
      (value "10µF")
      (footprint "eagle-import:C0805")
      (libsource (lib "eagle-import") (part "C-EUC0805"))
    )
    (comp (ref "C4")
      (value "33pF")
      (footprint "eagle-import:C0603")
      (libsource (lib "eagle-import") (part "C-EUC0603"))
    )
    (comp (ref "C5")
      (value "10µF")
      (footprint "eagle-import:C0805")
      (libsource (lib "eagle-import") (part "C-EUC0805"))
    )
    (comp (ref "C6")
      (value "10µF")
      (footprint "eagle-import:C0805")
      (libsource (lib "eagle-import") (part "C-EUC0805"))
    )
    (comp (ref "C30")
      (value "10µF")
      (footprint "eagle-import:C0805")
      (libsource (lib "eagle-import") (part "C-EUC0805"))
    )
    (comp (ref "C34")
      (value "1nF")
      (footprint "eagle-import:C0603")
      (libsource (lib "eagle-import") (part "C-EUC0603"))
    )
    (comp (ref "JP1")
      (value "PINHD-2X13")
      (footprint "eagle-import:2X13")
      (libsource (lib "eagle-import") (part "PINHD-2X13"))
    )
    (comp (ref "JP7")
      (value "PINHD-1X3M")
      (footprint "eagle-import:1X03M")
      (libsource (lib "eagle-import") (part "PINHD-1X3M"))
    )
    (comp (ref "R8")
      (value "10k")
      (footprint "eagle-import:R0603")
      (libsource (lib "eagle-import") (part "R-EU_R0603"))
    )
    (comp (ref "R9")
      (value "100k")
      (footprint "eagle-import:R0603")
      (libsource (lib "eagle-import") (part "R-EU_R0603"))
    )
    (comp (ref "R10")
      (value "100k")
      (footprint "eagle-import:R0603")
      (libsource (lib "eagle-import") (part "R-EU_R0603"))
    )
    (comp (ref "R19")
      (value "10k")
      (footprint "eagle-import:R0603")
      (libsource (lib "eagle-import") (part "R-EU_R0603"))
    )
    (comp (ref "R29")
      (value "47k")
      (footprint "eagle-import:R0603")
      (libsource (lib "eagle-import") (part "R-EU_R0603"))
    )
    (comp (ref "R32")
      (value "47k")
      (footprint "eagle-import:R0603")
      (libsource (lib "eagle-import") (part "R-EU_R0603"))
    )
    (comp (ref "R36")
      (value "47k")
      (footprint "eagle-import:R0603")
      (libsource (lib "eagle-import") (part "R-EU_R0603"))
    )
    (comp (ref "R38")
      (value "10k")
      (footprint "eagle-import:R0603")
      (libsource (lib "eagle-import") (part "R-EU_R0603"))
    )
    (comp (ref "R39")
      (value "10k")
      (footprint "eagle-import:R0603")
      (libsource (lib "eagle-import") (part "R-EU_R0603"))
    )
    (comp (ref "R44")
      (value "10k")
      (footprint "eagle-import:R0603")
      (libsource (lib "eagle-import") (part "R-EU_R0603"))
    )
    (comp (ref "R45")
      (value "10k")
      (footprint "eagle-import:R0603")
      (libsource (lib "eagle-import") (part "R-EU_R0603"))
    )
    (comp (ref "RN1")
      (value "4R-NEXB38V")
      (footprint "eagle-import:EXB38V")
      (libsource (lib "eagle-import") (part "4R-NEXB38V"))
    )
    (comp (ref "U$2")
      (value "RTL8723BS")
      (footprint "eagle-import:LGA")
      (libsource (lib "eagle-import") (part "RTL8723BS"))
    )
    (comp (ref "U$8")
      (value "NS2009")
      (footprint "eagle-import:MSOP10")
      (libsource (lib "eagle-import") (part "NS2009"))
    )
    (comp (ref "U1")
      (value "25F32006WSOI")
      (footprint "eagle-import:SO08-EIAJ")
      (libsource (lib "eagle-import") (part "SPI_FLASH-X25XXSMD1"))
    )
    (comp (ref "C40")
      (value "47pF")
      (footprint "eagle-import:C0603")
      (libsource (lib "eagle-import") (part "rcl_334_C-EUC0603"))
    )
    (comp (ref "C41")
      (value "47pF")
      (footprint "eagle-import:C0603")
      (libsource (lib "eagle-import") (part "rcl_334_C-EUC0603"))
    )
    (comp (ref "C42")
      (value "470pF")
      (footprint "eagle-import:C0603")
      (libsource (lib "eagle-import") (part "rcl_334_C-EUC0603"))
    )
    (comp (ref "C43")
      (value "10µF")
      (footprint "eagle-import:C0805")
      (libsource (lib "eagle-import") (part "rcl_334_C-EUC0805"))
    )
    (comp (ref "C44")
      (value "10µF")
      (footprint "eagle-import:C0805")
      (libsource (lib "eagle-import") (part "rcl_334_C-EUC0805"))
    )
    (comp (ref "C45")
      (value "10µF")
      (footprint "eagle-import:C0805")
      (libsource (lib "eagle-import") (part "rcl_334_C-EUC0805"))
    )
    (comp (ref "C46")
      (value "10µF")
      (footprint "eagle-import:C0805")
      (libsource (lib "eagle-import") (part "rcl_334_C-EUC0805"))
    )
    (comp (ref "C77")
      (value "100nF")
      (footprint "eagle-import:C0603")
      (libsource (lib "eagle-import") (part "rcl_334_C-EUC0603"))
    )
    (comp (ref "C78")
      (value "10µF")
      (footprint "eagle-import:C0805")
      (libsource (lib "eagle-import") (part "rcl_334_C-EUC0805"))
    )
    (comp (ref "C79")
      (value "100nF")
      (footprint "eagle-import:C0603")
      (libsource (lib "eagle-import") (part "rcl_334_C-EUC0603"))
    )
    (comp (ref "C80")
      (value "10µF")
      (footprint "eagle-import:C0805")
      (libsource (lib "eagle-import") (part "rcl_334_C-EUC0805"))
    )
    (comp (ref "C81")
      (value "100nF")
      (footprint "eagle-import:C0603")
      (libsource (lib "eagle-import") (part "rcl_334_C-EUC0603"))
    )
    (comp (ref "C82")
      (value "10µF")
      (footprint "eagle-import:C0805")
      (libsource (lib "eagle-import") (part "rcl_334_C-EUC0805"))
    )
    (comp (ref "C83")
      (value "100nF")
      (footprint "eagle-import:C0603")
      (libsource (lib "eagle-import") (part "rcl_334_C-EUC0603"))
    )
    (comp (ref "C84")
      (value "10µF")
      (footprint "eagle-import:C0805")
      (libsource (lib "eagle-import") (part "rcl_334_C-EUC0805"))
    )
    (comp (ref "Q3")
      (value "28.6363")
      (footprint "eagle-import:HC49_S")
      (libsource (lib "eagle-import") (part "crystal_204_CRYSTALHC49S"))
    )
    (comp (ref "Q4")
      (value "BSS123")
      (footprint "eagle-import:SOT23")
      (libsource (lib "eagle-import") (part "BSS123"))
    )
    (comp (ref "Q5")
      (value "BSS123")
      (footprint "eagle-import:SOT23")
      (libsource (lib "eagle-import") (part "BSS123"))
    )
    (comp (ref "R59")
      (value "390k")
      (footprint "eagle-import:R0603")
      (libsource (lib "eagle-import") (part "rcl_334_R-EU_R0603"))
    )
    (comp (ref "R60")
      (value "1k")
      (footprint "eagle-import:R0603")
      (libsource (lib "eagle-import") (part "rcl_334_R-EU_R0603"))
    )
    (comp (ref "R61")
      (value "3k3")
      (footprint "eagle-import:R0603")
      (libsource (lib "eagle-import") (part "rcl_334_R-EU_R0603"))
    )
    (comp (ref "R62")
      (value "3k3")
      (footprint "eagle-import:R0603")
      (libsource (lib "eagle-import") (part "rcl_334_R-EU_R0603"))
    )
    (comp (ref "R63")
      (value "10k")
      (footprint "eagle-import:R0603")
      (libsource (lib "eagle-import") (part "rcl_334_R-EU_R0603"))
    )
    (comp (ref "R64")
      (value "10k")
      (footprint "eagle-import:R0603")
      (libsource (lib "eagle-import") (part "rcl_334_R-EU_R0603"))
    )
    (comp (ref "R65")
      (value "3k3")
      (footprint "eagle-import:R0603")
      (libsource (lib "eagle-import") (part "rcl_334_R-EU_R0603"))
    )
    (comp (ref "R66")
      (value "100k")
      (footprint "eagle-import:R0603")
      (libsource (lib "eagle-import") (part "rcl_334_R-EU_R0603"))
    )
    (comp (ref "R67")
      (value "3k3")
      (footprint "eagle-import:R0603")
      (libsource (lib "eagle-import") (part "rcl_334_R-EU_R0603"))
    )
    (comp (ref "R68")
      (value "100k")
      (footprint "eagle-import:R0603")
      (libsource (lib "eagle-import") (part "rcl_334_R-EU_R0603"))
    )
    (comp (ref "U$5")
      (value "ADV7611")
      (footprint "eagle-import:QFP50P1210X1210X120-65T500")
      (libsource (lib "eagle-import") (part "ADV7611"))
    )
    (comp (ref "U$12")
      (value "HDMI-A")
      (footprint "eagle-import:HDMI_A")
      (libsource (lib "eagle-import") (part "HDMI-A"))
    )
    (comp (ref "U$13")
      (value "XC6210B332MR-G")
      (footprint "eagle-import:SOT-25")
      (libsource (lib "eagle-import") (part "XC6210"))
    )
    (comp (ref "U$14")
      (value "RT9013-18GB")
      (footprint "eagle-import:SOT-23-5")
      (libsource (lib "eagle-import") (part "RT9013"))
    )
    (comp (ref "J3")
      (value "40PINFPCH15-1LW")
      (footprint "eagle-import:XF2H-4015-1LW")
      (libsource (lib "eagle-import") (part "40PINFPC15-1LWH"))
    )
    (comp (ref "JP6")
      (value "OV7670")
      (footprint "eagle-import:2X09")
      (libsource (lib "eagle-import") (part "PINHD-2X9"))
    )
    (comp (ref "JP10")
      (value "OV2640")
      (footprint "eagle-import:2X10")
      (libsource (lib "eagle-import") (part "PINHD-2X10"))
    )
    (comp (ref "C32")
      (value "100nF")
      (footprint "eagle-import:C0603")
      (libsource (lib "eagle-import") (part "C-EUC0603"))
    )
    (comp (ref "C33")
      (value "100nF")
      (footprint "eagle-import:C0603")
      (libsource (lib "eagle-import") (part "C-EUC0603"))
    )
    (comp (ref "C35")
      (value "100nF")
      (footprint "eagle-import:C0603")
      (libsource (lib "eagle-import") (part "C-EUC0603"))
    )
    (comp (ref "R4")
      (value "17,8k")
      (footprint "eagle-import:R0603")
      (libsource (lib "eagle-import") (part "R-EU_R0603"))
    )
    (comp (ref "R5")
      (value "8,66k")
      (footprint "eagle-import:R0603")
      (libsource (lib "eagle-import") (part "R-EU_R0603"))
    )
    (comp (ref "R6")
      (value "4,32k")
      (footprint "eagle-import:R0603")
      (libsource (lib "eagle-import") (part "R-EU_R0603"))
    )
    (comp (ref "R7")
      (value "2,2k")
      (footprint "eagle-import:R0603")
      (libsource (lib "eagle-import") (part "R-EU_R0603"))
    )
    (comp (ref "R18")
      (value "1,05k")
      (footprint "eagle-import:R0603")
      (libsource (lib "eagle-import") (part "R-EU_R0603"))
    )
    (comp (ref "R31")
      (value "549")
      (footprint "eagle-import:R0603")
      (libsource (lib "eagle-import") (part "R-EU_R0603"))
    )
    (comp (ref "R33")
      (value "17,8k")
      (footprint "eagle-import:R0603")
      (libsource (lib "eagle-import") (part "R-EU_R0603"))
    )
    (comp (ref "R34")
      (value "8,66k")
      (footprint "eagle-import:R0603")
      (libsource (lib "eagle-import") (part "R-EU_R0603"))
    )
    (comp (ref "R35")
      (value "4,32k")
      (footprint "eagle-import:R0603")
      (libsource (lib "eagle-import") (part "R-EU_R0603"))
    )
    (comp (ref "R37")
      (value "2,2k")
      (footprint "eagle-import:R0603")
      (libsource (lib "eagle-import") (part "R-EU_R0603"))
    )
    (comp (ref "R46")
      (value "1,05k")
      (footprint "eagle-import:R0603")
      (libsource (lib "eagle-import") (part "R-EU_R0603"))
    )
    (comp (ref "R48")
      (value "549")
      (footprint "eagle-import:R0603")
      (libsource (lib "eagle-import") (part "R-EU_R0603"))
    )
    (comp (ref "R49")
      (value "17,8k")
      (footprint "eagle-import:R0603")
      (libsource (lib "eagle-import") (part "R-EU_R0603"))
    )
    (comp (ref "R50")
      (value "8,66k")
      (footprint "eagle-import:R0603")
      (libsource (lib "eagle-import") (part "R-EU_R0603"))
    )
    (comp (ref "R51")
      (value "4,32k")
      (footprint "eagle-import:R0603")
      (libsource (lib "eagle-import") (part "R-EU_R0603"))
    )
    (comp (ref "R54")
      (value "2,2k")
      (footprint "eagle-import:R0603")
      (libsource (lib "eagle-import") (part "R-EU_R0603"))
    )
    (comp (ref "R55")
      (value "1,05k")
      (footprint "eagle-import:R0603")
      (libsource (lib "eagle-import") (part "R-EU_R0603"))
    )
    (comp (ref "R56")
      (value "549")
      (footprint "eagle-import:R0603")
      (libsource (lib "eagle-import") (part "R-EU_R0603"))
    )
    (comp (ref "R57")
      (value "2K2")
      (footprint "eagle-import:R0603")
      (libsource (lib "eagle-import") (part "R-EU_R0603"))
    )
    (comp (ref "R58")
      (value "2K2")
      (footprint "eagle-import:R0603")
      (libsource (lib "eagle-import") (part "R-EU_R0603"))
    )
    (comp (ref "U2")
      (value "SN74ALVC244PW")
      (footprint "eagle-import:SOP65P640X120-20N")
      (libsource (lib "eagle-import") (part "SN74ALVC244PW"))
    )
    (comp (ref "U3")
      (value "SN74ALVC244PW")
      (footprint "eagle-import:SOP65P640X120-20N")
      (libsource (lib "eagle-import") (part "SN74ALVC244PW"))
    )
    (comp (ref "U4")
      (value "SN74ALVC244PW")
      (footprint "eagle-import:SOP65P640X120-20N")
      (libsource (lib "eagle-import") (part "SN74ALVC244PW"))
    )
    (comp (ref "U5")
      (value "BSS138TA")
      (footprint "eagle-import:SOT95P240X110-3N")
      (libsource (lib "eagle-import") (part "BSS138TA"))
    )
    (comp (ref "U6")
      (value "BSS138TA")
      (footprint "eagle-import:SOT95P240X110-3N")
      (libsource (lib "eagle-import") (part "BSS138TA"))
    )
    (comp (ref "X2")
      (value "F15HDH")
      (footprint "eagle-import:HDF15H")
      (libsource (lib "eagle-import") (part "F15HDH"))
    )
  )
  (nets
    (net (code "1") (name "+1V2") (class "Default")
      (node (ref "C52") (pin "1") (pinfunction "1_1") (pintype "passive"))
      (node (ref "C53") (pin "1") (pinfunction "1_1") (pintype "passive"))
      (node (ref "C54") (pin "1") (pinfunction "1_1") (pintype "passive"))
      (node (ref "C55") (pin "1") (pinfunction "1_1") (pintype "passive"))
      (node (ref "C56") (pin "1") (pinfunction "1_1") (pintype "passive"))
      (node (ref "C62") (pin "1") (pinfunction "1_1") (pintype "passive"))
      (node (ref "C63") (pin "1") (pinfunction "1_1") (pintype "passive"))
      (node (ref "C64") (pin "1") (pinfunction "1_1") (pintype "passive"))
      (node (ref "C65") (pin "1") (pinfunction "1_1") (pintype "passive"))
      (node (ref "C66") (pin "1") (pinfunction "1_1") (pintype "passive"))
      (node (ref "C67") (pin "1") (pinfunction "1_1") (pintype "passive"))
      (node (ref "R71") (pin "2") (pinfunction "2_2") (pintype "passive"))
      (node (ref "U$1") (pin "108") (pinfunction "VDD-SYS1_108") (pintype "bidirectional"))
      (node (ref "U$1") (pin "126") (pinfunction "VDD-SYS2_126") (pintype "bidirectional"))
      (node (ref "U$1") (pin "19") (pinfunction "VDD-SYS3_19") (pintype "bidirectional"))
      (node (ref "U$1") (pin "20") (pinfunction "VDD-CPU3_20") (pintype "bidirectional"))
      (node (ref "U$1") (pin "21") (pinfunction "VDD-CPU2_21") (pintype "bidirectional"))
      (node (ref "U$1") (pin "25") (pinfunction "VDD-CPU1_25") (pintype "bidirectional"))
      (node (ref "U$1") (pin "26") (pinfunction "VDD-CPU0_26") (pintype "bidirectional"))
      (node (ref "U$1") (pin "38") (pinfunction "VDD-CPU4_38") (pintype "bidirectional"))
      (node (ref "U$1") (pin "47") (pinfunction "VDD-CPU5_47") (pintype "bidirectional"))
      (node (ref "U$1") (pin "51") (pinfunction "VDD-CPU6_51") (pintype "bidirectional"))
      (node (ref "U$1") (pin "56") (pinfunction "VDD-CPU7_56") (pintype "bidirectional"))
      (node (ref "U$1") (pin "58") (pinfunction "VDD-SYS4_58") (pintype "bidirectional"))
      (node (ref "U$1") (pin "64") (pinfunction "VDD-SYS5_64") (pintype "bidirectional"))
      (node (ref "U$1") (pin "80") (pinfunction "VDD-SYS0_80") (pintype "bidirectional"))
      (node (ref "U$1") (pin "88") (pinfunction "EPHY_VDD_88") (pintype "bidirectional"))
    )
    (net (code "2") (name "+1V8") (class "Default")
      (node (ref "C14") (pin "2") (pinfunction "2_2") (pintype "passive"))
      (node (ref "C38") (pin "2") (pinfunction "2_2") (pintype "passive"))
      (node (ref "C39") (pin "1") (pinfunction "1_1") (pintype "passive"))
      (node (ref "C47") (pin "1") (pinfunction "1_1") (pintype "passive"))
      (node (ref "C50") (pin "1") (pinfunction "1_1") (pintype "passive"))
      (node (ref "C51") (pin "1") (pinfunction "1_1") (pintype "passive"))
      (node (ref "R13") (pin "2") (pinfunction "2_2") (pintype "passive"))
      (node (ref "R70") (pin "2") (pinfunction "2_2") (pintype "passive"))
      (node (ref "U$1") (pin "59") (pinfunction "VCC-DRAM8_59") (pintype "bidirectional"))
      (node (ref "U$1") (pin "60") (pinfunction "VCC-DRAM9_60") (pintype "bidirectional"))
      (node (ref "U$1") (pin "61") (pinfunction "VCC-DRAM10_61") (pintype "bidirectional"))
      (node (ref "U$1") (pin "62") (pinfunction "VCC-DRAM11_62") (pintype "bidirectional"))
      (node (ref "U$1") (pin "65") (pinfunction "VCC-DRAM0_65") (pintype "bidirectional"))
      (node (ref "U$1") (pin "66") (pinfunction "VCC-DRAM1_66") (pintype "bidirectional"))
      (node (ref "U$1") (pin "67") (pinfunction "VCC-DRAM2_67") (pintype "bidirectional"))
      (node (ref "U$1") (pin "68") (pinfunction "VCC-DRAM3_68") (pintype "bidirectional"))
      (node (ref "U$1") (pin "69") (pinfunction "VCC-DRAM4_69") (pintype "bidirectional"))
      (node (ref "U$1") (pin "70") (pinfunction "VCC-DRAM5_70") (pintype "bidirectional"))
      (node (ref "U$1") (pin "72") (pinfunction "VCC-DRAM6_72") (pintype "bidirectional"))
      (node (ref "U$1") (pin "79") (pinfunction "VCC-DRAM7_79") (pintype "bidirectional"))
    )
    (net (code "3") (name "+2V5") (class "Default")
      (node (ref "C76") (pin "1") (pinfunction "1_1") (pintype "passive"))
      (node (ref "JP3") (pin "1") (pinfunction "1_1") (pintype "passive"))
      (node (ref "U$6") (pin "5") (pinfunction "VOUT_5") (pintype "bidirectional"))
    )
    (net (code "4") (name "+3V3") (class "Default")
      (node (ref "C1") (pin "1") (pinfunction "1_1") (pintype "passive"))
      (node (ref "C2") (pin "1") (pinfunction "1_1") (pintype "passive"))
      (node (ref "C3") (pin "1") (pinfunction "1_1") (pintype "passive"))
      (node (ref "C30") (pin "1") (pinfunction "1_1") (pintype "passive"))
      (node (ref "C31") (pin "1") (pinfunction "1_1") (pintype "passive"))
      (node (ref "C32") (pin "2") (pinfunction "2_2") (pintype "passive"))
      (node (ref "C33") (pin "2") (pinfunction "2_2") (pintype "passive"))
      (node (ref "C35") (pin "2") (pinfunction "2_2") (pintype "passive"))
      (node (ref "C5") (pin "1") (pinfunction "1_1") (pintype "passive"))
      (node (ref "C57") (pin "1") (pinfunction "1_1") (pintype "passive"))
      (node (ref "C58") (pin "1") (pinfunction "1_1") (pintype "passive"))
      (node (ref "C59") (pin "1") (pinfunction "1_1") (pintype "passive"))
      (node (ref "C6") (pin "1") (pinfunction "1_1") (pintype "passive"))
      (node (ref "C60") (pin "1") (pinfunction "1_1") (pintype "passive"))
      (node (ref "C61") (pin "1") (pinfunction "1_1") (pintype "passive"))
      (node (ref "C69") (pin "1") (pinfunction "1_1") (pintype "passive"))
      (node (ref "C70") (pin "1") (pinfunction "1_1") (pintype "passive"))
      (node (ref "C9") (pin "1") (pinfunction "1_1") (pintype "passive"))
      (node (ref "J1") (pin "4") (pinfunction "VDD_4") (pintype "power_in"))
      (node (ref "J3") (pin "31") (pinfunction "MS_31") (pintype "passive"))
      (node (ref "J3") (pin "4") (pinfunction "MS_4") (pintype "passive"))
      (node (ref "J4") (pin "1") (pinfunction "15_1") (pintype "passive"))
      (node (ref "JP1") (pin "1") (pinfunction "1_1") (pintype "passive"))
      (node (ref "JP1") (pin "17") (pinfunction "17_17") (pintype "passive"))
      (node (ref "JP10") (pin "1") (pinfunction "1_1") (pintype "passive"))
      (node (ref "JP10") (pin "17") (pinfunction "17_17") (pintype "passive"))
      (node (ref "JP3") (pin "3") (pinfunction "3_3") (pintype "passive"))
      (node (ref "JP5") (pin "1") (pinfunction "1_1") (pintype "passive"))
      (node (ref "JP6") (pin "1") (pinfunction "1_1") (pintype "passive"))
      (node (ref "JP6") (pin "17") (pinfunction "17_17") (pintype "passive"))
      (node (ref "L2") (pin "1") (pinfunction "1_1") (pintype "passive"))
      (node (ref "R1") (pin "2") (pinfunction "2_2") (pintype "passive"))
      (node (ref "R10") (pin "2") (pinfunction "2_2") (pintype "passive"))
      (node (ref "R11") (pin "2") (pinfunction "2_2") (pintype "passive"))
      (node (ref "R19") (pin "2") (pinfunction "2_2") (pintype "passive"))
      (node (ref "R2") (pin "2") (pinfunction "2_2") (pintype "passive"))
      (node (ref "R32") (pin "1") (pinfunction "1_1") (pintype "passive"))
      (node (ref "R36") (pin "1") (pinfunction "1_1") (pintype "passive"))
      (node (ref "R38") (pin "1") (pinfunction "1_1") (pintype "passive"))
      (node (ref "R39") (pin "1") (pinfunction "1_1") (pintype "passive"))
      (node (ref "R69") (pin "2") (pinfunction "2_2") (pintype "passive"))
      (node (ref "R8") (pin "2") (pinfunction "2_2") (pintype "passive"))
      (node (ref "R9") (pin "1") (pinfunction "1_1") (pintype "passive"))
      (node (ref "RN1") (pin "1") (pinfunction "1_1") (pintype "passive"))
      (node (ref "RN1") (pin "2") (pinfunction "1_2") (pintype "passive"))
      (node (ref "RN1") (pin "3") (pinfunction "1_3") (pintype "passive"))
      (node (ref "RN1") (pin "4") (pinfunction "1_4") (pintype "passive"))
      (node (ref "RN2") (pin "1") (pinfunction "1_1") (pintype "passive"))
      (node (ref "RN2") (pin "2") (pinfunction "1_2") (pintype "passive"))
      (node (ref "RN2") (pin "3") (pinfunction "1_3") (pintype "passive"))
      (node (ref "RN2") (pin "4") (pinfunction "1_4") (pintype "passive"))
      (node (ref "U$1") (pin "104") (pinfunction "VCC-0_104") (pintype "bidirectional"))
      (node (ref "U$1") (pin "109") (pinfunction "VCC-USB_109") (pintype "bidirectional"))
      (node (ref "U$1") (pin "122") (pinfunction "HPVCCIN_122") (pintype "bidirectional"))
      (node (ref "U$1") (pin "127") (pinfunction "VCC-1_127") (pintype "bidirectional"))
      (node (ref "U$1") (pin "50") (pinfunction "VCC-3_50") (pintype "bidirectional"))
      (node (ref "U$1") (pin "57") (pinfunction "VCC-2_57") (pintype "bidirectional"))
      (node (ref "U$1") (pin "85") (pinfunction "VCC-MCSI_85") (pintype "bidirectional"))
      (node (ref "U$1") (pin "93") (pinfunction "EPHY_VCC_93") (pintype "bidirectional"))
      (node (ref "U$2") (pin "P$22") (pinfunction "VDD_IO_P$22") (pintype "bidirectional"))
      (node (ref "U$2") (pin "P$9") (pinfunction "VCC_P$9") (pintype "bidirectional"))
      (node (ref "U$6") (pin "1") (pinfunction "VIN_1") (pintype "bidirectional"))
      (node (ref "U$6") (pin "3") (pinfunction "CE_3") (pintype "bidirectional"))
      (node (ref "U$8") (pin "1") (pinfunction "VDD_1") (pintype "bidirectional"))
      (node (ref "U1") (pin "3") (pinfunction "WP_3") (pintype "bidirectional"))
      (node (ref "U1") (pin "7") (pinfunction "HOLD_7") (pintype "bidirectional"))
      (node (ref "U1") (pin "8") (pinfunction "VCC_8") (pintype "power_in"))
      (node (ref "U2") (pin "20") (pinfunction "VCC_20") (pintype "power_in"))
      (node (ref "U3") (pin "20") (pinfunction "VCC_20") (pintype "power_in"))
      (node (ref "U4") (pin "20") (pinfunction "VCC_20") (pintype "power_in"))
      (node (ref "U5") (pin "1") (pinfunction "G_1") (pintype "passive"))
      (node (ref "U6") (pin "1") (pinfunction "G_1") (pintype "passive"))
    )
    (net (code "5") (name "+3V3A") (class "Default")
      (node (ref "C16") (pin "2") (pinfunction "2_2") (pintype "passive"))
      (node (ref "C26") (pin "2") (pinfunction "2_2") (pintype "passive"))
      (node (ref "C37") (pin "1") (pinfunction "1_1") (pintype "passive"))
      (node (ref "C71") (pin "1") (pinfunction "1_1") (pintype "passive"))
      (node (ref "IC1") (pin "2") (pinfunction "OUT_2") (pintype "passive"))
      (node (ref "R29") (pin "2") (pinfunction "2_2") (pintype "passive"))
      (node (ref "R30") (pin "2") (pinfunction "2_2") (pintype "passive"))
      (node (ref "U$1") (pin "115") (pinfunction "AVCC_115") (pintype "bidirectional"))
      (node (ref "U$1") (pin "76") (pinfunction "VCC-PLL_76") (pintype "bidirectional"))
    )
    (net (code "6") (name "+3V3ANC") (class "Default")
      (node (ref "IC1") (pin "4") (pinfunction "IN1_4") (pintype "input"))
    )
    (net (code "7") (name "+5V") (class "Default")
      (node (ref "C36") (pin "1") (pinfunction "1_1") (pintype "passive"))
      (node (ref "C44") (pin "1") (pinfunction "1_1") (pintype "passive"))
      (node (ref "C73") (pin "1") (pinfunction "1_1") (pintype "passive"))
      (node (ref "C84") (pin "1") (pinfunction "1_1") (pintype "passive"))
      (node (ref "IC1") (pin "3") (pinfunction "IN_3") (pintype "input"))
      (node (ref "JP1") (pin "2") (pinfunction "2_2") (pintype "passive"))
      (node (ref "JP1") (pin "4") (pinfunction "4_4") (pintype "passive"))
      (node (ref "L1") (pin "P$1") (pinfunction "1_P$1") (pintype "passive"))
      (node (ref "Q4") (pin "1") (pinfunction "G_1") (pintype "passive"))
      (node (ref "R16") (pin "2") (pinfunction "2_2") (pintype "passive"))
      (node (ref "R57") (pin "1") (pinfunction "1_1") (pintype "passive"))
      (node (ref "R58") (pin "1") (pinfunction "1_1") (pintype "passive"))
      (node (ref "U$10") (pin "P$2") (pinfunction "VIN+_P$2") (pintype "input"))
      (node (ref "U$11") (pin "P$2") (pinfunction "VIN+_P$2") (pintype "input"))
      (node (ref "U$13") (pin "1") (pinfunction "CE_1") (pintype "bidirectional"))
      (node (ref "U$13") (pin "3") (pinfunction "VIN_3") (pintype "bidirectional"))
      (node (ref "U$14") (pin "1") (pinfunction "VIN_1") (pintype "bidirectional"))
      (node (ref "U$15") (pin "1") (pinfunction "1_1") (pintype "input"))
      (node (ref "U$4") (pin "P$2") (pinfunction "VIN+_P$2") (pintype "input"))
      (node (ref "U$7") (pin "2") (pinfunction "S_2") (pintype "passive"))
      (node (ref "U$9") (pin "4") (pinfunction "EN_4") (pintype "bidirectional"))
      (node (ref "U$9") (pin "6") (pinfunction "IN_6") (pintype "bidirectional"))
      (node (ref "X1") (pin "VBUS") (pinfunction "VBUS_VBUS") (pintype "power_in"))
    )
    (net (code "8") (name "ADV7611_1V8") (class "Default")
      (node (ref "C45") (pin "1") (pinfunction "1_1") (pintype "passive"))
      (node (ref "C46") (pin "1") (pinfunction "1_1") (pintype "passive"))
      (node (ref "C77") (pin "1") (pinfunction "1_1") (pintype "passive"))
      (node (ref "C78") (pin "1") (pinfunction "1_1") (pintype "passive"))
      (node (ref "C79") (pin "1") (pinfunction "1_1") (pintype "passive"))
      (node (ref "U$14") (pin "5") (pinfunction "VOUT_5") (pintype "bidirectional"))
      (node (ref "U$5") (pin "14") (pinfunction "CVDD2_14") (pintype "bidirectional"))
      (node (ref "U$5") (pin "2") (pinfunction "CVDD1_2") (pintype "bidirectional"))
      (node (ref "U$5") (pin "24") (pinfunction "DVDD1_24") (pintype "bidirectional"))
      (node (ref "U$5") (pin "40") (pinfunction "DVDD2_40") (pintype "bidirectional"))
      (node (ref "U$5") (pin "52") (pinfunction "DVDD3_52") (pintype "bidirectional"))
      (node (ref "U$5") (pin "57") (pinfunction "PVDD_57") (pintype "bidirectional"))
      (node (ref "U$5") (pin "60") (pinfunction "DVDD4_60") (pintype "bidirectional"))
    )
    (net (code "9") (name "ADV7611_3V3") (class "Default")
      (node (ref "C43") (pin "1") (pinfunction "1_1") (pintype "passive"))
      (node (ref "C80") (pin "1") (pinfunction "1_1") (pintype "passive"))
      (node (ref "C81") (pin "1") (pinfunction "1_1") (pintype "passive"))
      (node (ref "C82") (pin "1") (pinfunction "1_1") (pintype "passive"))
      (node (ref "C83") (pin "1") (pinfunction "1_1") (pintype "passive"))
      (node (ref "R65") (pin "1") (pinfunction "1_1") (pintype "passive"))
      (node (ref "R67") (pin "2") (pinfunction "2_2") (pintype "passive"))
      (node (ref "R68") (pin "2") (pinfunction "2_2") (pintype "passive"))
      (node (ref "U$13") (pin "5") (pinfunction "VOUT_5") (pintype "bidirectional"))
      (node (ref "U$5") (pin "11") (pinfunction "TVDD3_11") (pintype "bidirectional"))
      (node (ref "U$5") (pin "23") (pinfunction "DVDDIO1_23") (pintype "bidirectional"))
      (node (ref "U$5") (pin "34") (pinfunction "DVDDIO2_34") (pintype "bidirectional"))
      (node (ref "U$5") (pin "44") (pinfunction "DVDDIO3_44") (pintype "bidirectional"))
      (node (ref "U$5") (pin "5") (pinfunction "TVDD1_5") (pintype "bidirectional"))
      (node (ref "U$5") (pin "56") (pinfunction "RESET_56") (pintype "bidirectional"))
      (node (ref "U$5") (pin "8") (pinfunction "TVDD2_8") (pintype "bidirectional"))
    )
    (net (code "10") (name "ADV7611_INT") (class "Default")
      (node (ref "U$5") (pin "55") (pinfunction "INT1_55") (pintype "bidirectional"))
    )
    (net (code "11") (name "BT_H_WK") (class "Default")
      (node (ref "U$2") (pin "P$7") (pinfunction "BT_H_WK_P$7") (pintype "bidirectional"))
    )
    (net (code "12") (name "BT_WK") (class "Default")
      (node (ref "U$2") (pin "P$6") (pinfunction "BT_WK_P$6") (pintype "bidirectional"))
    )
    (net (code "13") (name "CEC") (class "Default")
      (node (ref "U$12") (pin "P$13") (pinfunction "CEC_P$13") (pintype "bidirectional"))
      (node (ref "U$5") (pin "61") (pinfunction "CEC_61") (pintype "bidirectional"))
    )
    (net (code "14") (name "CSI_D0{slash}LCD_D2") (class "Default")
      (node (ref "J3") (pin "23") (pinfunction "MS_23") (pintype "passive"))
      (node (ref "U$1") (pin "33") (pinfunction "PE4/CSI-D0/LCD-D2_33") (pintype "bidirectional"))
      (node (ref "U$5") (pin "33") (pinfunction "P8_33") (pintype "bidirectional"))
      (node (ref "U2") (pin "6") (pinfunction "1A3_6") (pintype "input"))
    )
    (net (code "15") (name "CSI_D1{slash}LCD_D3") (class "Default")
      (node (ref "J3") (pin "24") (pinfunction "MS_24") (pintype "passive"))
      (node (ref "U$1") (pin "32") (pinfunction "PE5/CSI-D1/-LCD-D3_32") (pintype "bidirectional"))
      (node (ref "U$5") (pin "32") (pinfunction "P9_32") (pintype "bidirectional"))
      (node (ref "U2") (pin "8") (pinfunction "1A4_8") (pintype "input"))
    )
    (net (code "16") (name "CSI_D2{slash}LCD_D4") (class "Default")
      (node (ref "J3") (pin "25") (pinfunction "MS_25") (pintype "passive"))
      (node (ref "JP10") (pin "20") (pinfunction "20_20") (pintype "passive"))
      (node (ref "U$1") (pin "31") (pinfunction "PE6/CSI-D2/LCD-D4_31") (pintype "bidirectional"))
      (node (ref "U$5") (pin "31") (pinfunction "P10_31") (pintype "bidirectional"))
      (node (ref "U2") (pin "11") (pinfunction "2A1_11") (pintype "input"))
    )
    (net (code "17") (name "CSI_D3{slash}LCD_D5") (class "Default")
      (node (ref "J3") (pin "26") (pinfunction "MS_26") (pintype "passive"))
      (node (ref "JP10") (pin "19") (pinfunction "19_19") (pintype "passive"))
      (node (ref "U$1") (pin "30") (pinfunction "PE7/CSI-D3/LCD-D5_30") (pintype "bidirectional"))
      (node (ref "U$5") (pin "30") (pinfunction "P11_30") (pintype "bidirectional"))
      (node (ref "U2") (pin "13") (pinfunction "2A2_13") (pintype "input"))
    )
    (net (code "18") (name "CSI_D4{slash}LCD_D6") (class "Default")
      (node (ref "J3") (pin "27") (pinfunction "MS_27") (pintype "passive"))
      (node (ref "JP10") (pin "16") (pinfunction "16_16") (pintype "passive"))
      (node (ref "JP6") (pin "16") (pinfunction "16_16") (pintype "passive"))
      (node (ref "U$1") (pin "28") (pinfunction "PE8/CSI-D4/LCD-D6_28") (pintype "bidirectional"))
      (node (ref "U$5") (pin "29") (pinfunction "P12_29") (pintype "bidirectional"))
      (node (ref "U2") (pin "15") (pinfunction "2A3_15") (pintype "input"))
    )
    (net (code "19") (name "CSI_D5{slash}LCD_D7") (class "Default")
      (node (ref "J3") (pin "28") (pinfunction "MS_28") (pintype "passive"))
      (node (ref "JP10") (pin "15") (pinfunction "15_15") (pintype "passive"))
      (node (ref "JP6") (pin "15") (pinfunction "15_15") (pintype "passive"))
      (node (ref "U$1") (pin "27") (pinfunction "PE9/CSI-D5/LCD-D7_27") (pintype "bidirectional"))
      (node (ref "U$5") (pin "28") (pinfunction "P13_28") (pintype "bidirectional"))
      (node (ref "U2") (pin "17") (pinfunction "2A4_17") (pintype "input"))
    )
    (net (code "20") (name "CSI_D6{slash}LCD_D10") (class "Default")
      (node (ref "J3") (pin "15") (pinfunction "MS_15") (pintype "passive"))
      (node (ref "JP10") (pin "14") (pinfunction "14_14") (pintype "passive"))
      (node (ref "JP6") (pin "14") (pinfunction "14_14") (pintype "passive"))
      (node (ref "U$1") (pin "24") (pinfunction "PE10/CSI-D6/LCD-D10_24") (pintype "bidirectional"))
      (node (ref "U$5") (pin "27") (pinfunction "P14_27") (pintype "bidirectional"))
      (node (ref "U3") (pin "6") (pinfunction "1A3_6") (pintype "input"))
    )
    (net (code "21") (name "CSI_D7{slash}LCD_D11") (class "Default")
      (node (ref "J3") (pin "16") (pinfunction "MS_16") (pintype "passive"))
      (node (ref "JP10") (pin "13") (pinfunction "13_13") (pintype "passive"))
      (node (ref "JP6") (pin "13") (pinfunction "13_13") (pintype "passive"))
      (node (ref "U$1") (pin "23") (pinfunction "PE11/CSI-D7/LCD-D11_23") (pintype "bidirectional"))
      (node (ref "U$5") (pin "26") (pinfunction "P15_26") (pintype "bidirectional"))
      (node (ref "U3") (pin "8") (pinfunction "1A4_8") (pintype "input"))
    )
    (net (code "22") (name "CSI_D8{slash}LCD_D12") (class "Default")
      (node (ref "J3") (pin "17") (pinfunction "MS_17") (pintype "passive"))
      (node (ref "JP10") (pin "12") (pinfunction "12_12") (pintype "passive"))
      (node (ref "JP6") (pin "12") (pinfunction "12_12") (pintype "passive"))
      (node (ref "U$1") (pin "22") (pinfunction "PE12/CSI-D8/LCD-D12_22") (pintype "bidirectional"))
      (node (ref "U$5") (pin "43") (pinfunction "P0_43") (pintype "bidirectional"))
      (node (ref "U3") (pin "11") (pinfunction "2A1_11") (pintype "input"))
    )
    (net (code "23") (name "CSI_D9{slash}LCD_D13") (class "Default")
      (node (ref "J3") (pin "18") (pinfunction "MS_18") (pintype "passive"))
      (node (ref "JP10") (pin "11") (pinfunction "11_11") (pintype "passive"))
      (node (ref "JP6") (pin "11") (pinfunction "11_11") (pintype "passive"))
      (node (ref "U$1") (pin "18") (pinfunction "PE13/CSI-D9/LCD-D13_18") (pintype "bidirectional"))
      (node (ref "U$5") (pin "42") (pinfunction "P1_42") (pintype "bidirectional"))
      (node (ref "U3") (pin "13") (pinfunction "2A2_13") (pintype "input"))
    )
    (net (code "24") (name "CSI_D10{slash}LCD_D14") (class "Default")
      (node (ref "J3") (pin "19") (pinfunction "MS_19") (pintype "passive"))
      (node (ref "JP10") (pin "10") (pinfunction "10_10") (pintype "passive"))
      (node (ref "JP6") (pin "10") (pinfunction "10_10") (pintype "passive"))
      (node (ref "U$1") (pin "17") (pinfunction "PE14/CSI-D10/LCD-D14_17") (pintype "bidirectional"))
      (node (ref "U$5") (pin "41") (pinfunction "P2_41") (pintype "bidirectional"))
      (node (ref "U3") (pin "15") (pinfunction "2A3_15") (pintype "input"))
    )
    (net (code "25") (name "CSI_D11{slash}LCD_D15") (class "Default")
      (node (ref "J3") (pin "20") (pinfunction "MS_20") (pintype "passive"))
      (node (ref "JP10") (pin "9") (pinfunction "9_9") (pintype "passive"))
      (node (ref "JP6") (pin "9") (pinfunction "9_9") (pintype "passive"))
      (node (ref "U$1") (pin "16") (pinfunction "PE15/CSI-D11/LCD-D15_16") (pintype "bidirectional"))
      (node (ref "U$5") (pin "39") (pinfunction "P3_39") (pintype "bidirectional"))
      (node (ref "U3") (pin "17") (pinfunction "2A4_17") (pintype "input"))
    )
    (net (code "26") (name "CSI_D12{slash}LCD_D18") (class "Default")
      (node (ref "J3") (pin "7") (pinfunction "MS_7") (pintype "passive"))
      (node (ref "U$1") (pin "15") (pinfunction "PE16/CSI-D12/LCD-D18_15") (pintype "bidirectional"))
      (node (ref "U$5") (pin "38") (pinfunction "P4_38") (pintype "bidirectional"))
      (node (ref "U4") (pin "6") (pinfunction "1A3_6") (pintype "input"))
    )
    (net (code "27") (name "CSI_D13{slash}LCD_D19") (class "Default")
      (node (ref "J3") (pin "8") (pinfunction "MS_8") (pintype "passive"))
      (node (ref "U$1") (pin "14") (pinfunction "PE17/CSI-D13/LCD-D19_14") (pintype "bidirectional"))
      (node (ref "U$5") (pin "37") (pinfunction "P5_37") (pintype "bidirectional"))
      (node (ref "U4") (pin "8") (pinfunction "1A4_8") (pintype "input"))
    )
    (net (code "28") (name "CSI_D14{slash}LCD_D20") (class "Default")
      (node (ref "J3") (pin "9") (pinfunction "MS_9") (pintype "passive"))
      (node (ref "U$1") (pin "13") (pinfunction "PE18/CSI-D14/LCD-D20_13") (pintype "bidirectional"))
      (node (ref "U$5") (pin "36") (pinfunction "P6_36") (pintype "bidirectional"))
      (node (ref "U4") (pin "11") (pinfunction "2A1_11") (pintype "input"))
    )
    (net (code "29") (name "CSI_D15{slash}LCD_D21") (class "Default")
      (node (ref "J3") (pin "10") (pinfunction "MS_10") (pintype "passive"))
      (node (ref "U$1") (pin "11") (pinfunction "PE19/CSI-D15/LCD-D21_11") (pintype "bidirectional"))
      (node (ref "U$5") (pin "35") (pinfunction "P7_35") (pintype "bidirectional"))
      (node (ref "U4") (pin "13") (pinfunction "2A2_13") (pintype "input"))
    )
    (net (code "30") (name "CSI_HSYNC{slash}LCD_HSYNC") (class "Default")
      (node (ref "J3") (pin "32") (pinfunction "MS_32") (pintype "passive"))
      (node (ref "JP10") (pin "6") (pinfunction "6_6") (pintype "passive"))
      (node (ref "JP6") (pin "6") (pinfunction "6_6") (pintype "passive"))
      (node (ref "U$1") (pin "35") (pinfunction "PE2/CSI-HSYNC/LCD-HSYNC_35") (pintype "bidirectional"))
      (node (ref "U$5") (pin "46") (pinfunction "HSYNC_46") (pintype "bidirectional"))
      (node (ref "U6") (pin "2") (pinfunction "S_2") (pintype "passive"))
    )
    (net (code "31") (name "CSI_MCLK{slash}LCD_DE") (class "Default")
      (node (ref "J3") (pin "34") (pinfunction "MS_34") (pintype "passive"))
      (node (ref "JP10") (pin "8") (pinfunction "8_8") (pintype "passive"))
      (node (ref "JP6") (pin "8") (pinfunction "8_8") (pintype "passive"))
      (node (ref "U$1") (pin "36") (pinfunction "PE1/CSI-MCLK/LCD-DE_36") (pintype "bidirectional"))
      (node (ref "U$5") (pin "45") (pinfunction "DE_45") (pintype "bidirectional"))
    )
    (net (code "32") (name "CSI_PCLK{slash}LCD_CLK") (class "Default")
      (node (ref "J3") (pin "30") (pinfunction "MS_30") (pintype "passive"))
      (node (ref "JP10") (pin "7") (pinfunction "7_7") (pintype "passive"))
      (node (ref "JP6") (pin "7") (pinfunction "7_7") (pintype "passive"))
      (node (ref "U$1") (pin "37") (pinfunction "PE0/CSI-CLK-/LCD-CLK_37") (pintype "bidirectional"))
      (node (ref "U$5") (pin "25") (pinfunction "LLC_25") (pintype "bidirectional"))
    )
    (net (code "33") (name "CSI_VSYNC{slash}LCD_VSYNC") (class "Default")
      (node (ref "J3") (pin "33") (pinfunction "MS_33") (pintype "passive"))
      (node (ref "JP10") (pin "5") (pinfunction "5_5") (pintype "passive"))
      (node (ref "JP6") (pin "5") (pinfunction "5_5") (pintype "passive"))
      (node (ref "U$1") (pin "34") (pinfunction "PE3/CSI-VSYNC/LCD-VSYNC_34") (pintype "bidirectional"))
      (node (ref "U$5") (pin "47") (pinfunction "VS/FIELD/ALSB_47") (pintype "bidirectional"))
      (node (ref "U5") (pin "2") (pinfunction "S_2") (pintype "passive"))
    )
    (net (code "34") (name "EN_1V8") (class "Default")
      (node (ref "C42") (pin "1") (pinfunction "1_1") (pintype "passive"))
      (node (ref "R68") (pin "1") (pinfunction "1_1") (pintype "passive"))
      (node (ref "U$14") (pin "3") (pinfunction "EN_3") (pintype "bidirectional"))
    )
    (net (code "35") (name "EPHY_RXN") (class "Default")
      (node (ref "R41") (pin "1") (pinfunction "1_1") (pintype "passive"))
      (node (ref "U$1") (pin "89") (pinfunction "EPHY_RXN_89") (pintype "bidirectional"))
      (node (ref "U$3") (pin "6") (pinfunction "RD-_6") (pintype "bidirectional"))
    )
    (net (code "36") (name "EPHY_RXP") (class "Default")
      (node (ref "R40") (pin "1") (pinfunction "1_1") (pintype "passive"))
      (node (ref "U$1") (pin "90") (pinfunction "EPHY_RXP_90") (pintype "bidirectional"))
      (node (ref "U$3") (pin "3") (pinfunction "RD+_3") (pintype "bidirectional"))
    )
    (net (code "37") (name "EPHY_TXN") (class "Default")
      (node (ref "R43") (pin "1") (pinfunction "1_1") (pintype "passive"))
      (node (ref "U$1") (pin "91") (pinfunction "EPHY_TXN_91") (pintype "bidirectional"))
      (node (ref "U$3") (pin "2") (pinfunction "TD-_2") (pintype "bidirectional"))
    )
    (net (code "38") (name "EPHY_TXP") (class "Default")
      (node (ref "R42") (pin "1") (pinfunction "1_1") (pintype "passive"))
      (node (ref "U$1") (pin "92") (pinfunction "EPHY_TXP_92") (pintype "bidirectional"))
      (node (ref "U$3") (pin "1") (pinfunction "TD+_1") (pintype "bidirectional"))
    )
    (net (code "39") (name "GND") (class "Default")
      (node (ref "ANT2") (pin "GND1") (pinfunction "GND1_GND1") (pintype "bidirectional"))
      (node (ref "ANT2") (pin "GND2") (pinfunction "GND2_GND2") (pintype "bidirectional"))
      (node (ref "C1") (pin "2") (pinfunction "2_2") (pintype "passive"))
      (node (ref "C10") (pin "2") (pinfunction "2_2") (pintype "passive"))
      (node (ref "C11") (pin "1") (pinfunction "1_1") (pintype "passive"))
      (node (ref "C12") (pin "1") (pinfunction "1_1") (pintype "passive"))
      (node (ref "C13") (pin "2") (pinfunction "2_2") (pintype "passive"))
      (node (ref "C15") (pin "1") (pinfunction "1_1") (pintype "passive"))
      (node (ref "C16") (pin "1") (pinfunction "1_1") (pintype "passive"))
      (node (ref "C17") (pin "2") (pinfunction "2_2") (pintype "passive"))
      (node (ref "C2") (pin "2") (pinfunction "2_2") (pintype "passive"))
      (node (ref "C20") (pin "1") (pinfunction "1_1") (pintype "passive"))
      (node (ref "C21") (pin "1") (pinfunction "1_1") (pintype "passive"))
      (node (ref "C22") (pin "2") (pinfunction "2_2") (pintype "passive"))
      (node (ref "C23") (pin "1") (pinfunction "1_1") (pintype "passive"))
      (node (ref "C24") (pin "1") (pinfunction "1_1") (pintype "passive"))
      (node (ref "C26") (pin "1") (pinfunction "1_1") (pintype "passive"))
      (node (ref "C29") (pin "1") (pinfunction "1_1") (pintype "passive"))
      (node (ref "C3") (pin "2") (pinfunction "2_2") (pintype "passive"))
      (node (ref "C30") (pin "2") (pinfunction "2_2") (pintype "passive"))
      (node (ref "C31") (pin "2") (pinfunction "2_2") (pintype "passive"))
      (node (ref "C32") (pin "1") (pinfunction "1_1") (pintype "passive"))
      (node (ref "C33") (pin "1") (pinfunction "1_1") (pintype "passive"))
      (node (ref "C34") (pin "1") (pinfunction "1_1") (pintype "passive"))
      (node (ref "C35") (pin "1") (pinfunction "1_1") (pintype "passive"))
      (node (ref "C36") (pin "2") (pinfunction "2_2") (pintype "passive"))
      (node (ref "C37") (pin "2") (pinfunction "2_2") (pintype "passive"))
      (node (ref "C38") (pin "1") (pinfunction "1_1") (pintype "passive"))
      (node (ref "C39") (pin "2") (pinfunction "2_2") (pintype "passive"))
      (node (ref "C40") (pin "2") (pinfunction "2_2") (pintype "passive"))
      (node (ref "C41") (pin "2") (pinfunction "2_2") (pintype "passive"))
      (node (ref "C42") (pin "2") (pinfunction "2_2") (pintype "passive"))
      (node (ref "C43") (pin "2") (pinfunction "2_2") (pintype "passive"))
      (node (ref "C44") (pin "2") (pinfunction "2_2") (pintype "passive"))
      (node (ref "C45") (pin "2") (pinfunction "2_2") (pintype "passive"))
      (node (ref "C46") (pin "2") (pinfunction "2_2") (pintype "passive"))
      (node (ref "C47") (pin "2") (pinfunction "2_2") (pintype "passive"))
      (node (ref "C48") (pin "2") (pinfunction "2_2") (pintype "passive"))
      (node (ref "C49") (pin "2") (pinfunction "2_2") (pintype "passive"))
      (node (ref "C5") (pin "2") (pinfunction "2_2") (pintype "passive"))
      (node (ref "C50") (pin "2") (pinfunction "2_2") (pintype "passive"))
      (node (ref "C51") (pin "2") (pinfunction "2_2") (pintype "passive"))
      (node (ref "C52") (pin "2") (pinfunction "2_2") (pintype "passive"))
      (node (ref "C53") (pin "2") (pinfunction "2_2") (pintype "passive"))
      (node (ref "C54") (pin "2") (pinfunction "2_2") (pintype "passive"))
      (node (ref "C55") (pin "2") (pinfunction "2_2") (pintype "passive"))
      (node (ref "C56") (pin "2") (pinfunction "2_2") (pintype "passive"))
      (node (ref "C57") (pin "2") (pinfunction "2_2") (pintype "passive"))
      (node (ref "C58") (pin "2") (pinfunction "2_2") (pintype "passive"))
      (node (ref "C59") (pin "2") (pinfunction "2_2") (pintype "passive"))
      (node (ref "C6") (pin "2") (pinfunction "2_2") (pintype "passive"))
      (node (ref "C60") (pin "2") (pinfunction "2_2") (pintype "passive"))
      (node (ref "C61") (pin "2") (pinfunction "2_2") (pintype "passive"))
      (node (ref "C62") (pin "2") (pinfunction "2_2") (pintype "passive"))
      (node (ref "C63") (pin "2") (pinfunction "2_2") (pintype "passive"))
      (node (ref "C64") (pin "2") (pinfunction "2_2") (pintype "passive"))
      (node (ref "C65") (pin "2") (pinfunction "2_2") (pintype "passive"))
      (node (ref "C66") (pin "2") (pinfunction "2_2") (pintype "passive"))
      (node (ref "C67") (pin "2") (pinfunction "2_2") (pintype "passive"))
      (node (ref "C69") (pin "2") (pinfunction "2_2") (pintype "passive"))
      (node (ref "C7") (pin "2") (pinfunction "2_2") (pintype "passive"))
      (node (ref "C70") (pin "2") (pinfunction "2_2") (pintype "passive"))
      (node (ref "C71") (pin "2") (pinfunction "2_2") (pintype "passive"))
      (node (ref "C73") (pin "2") (pinfunction "2_2") (pintype "passive"))
      (node (ref "C74") (pin "2") (pinfunction "2_2") (pintype "passive"))
      (node (ref "C75") (pin "2") (pinfunction "2_2") (pintype "passive"))
      (node (ref "C76") (pin "2") (pinfunction "2_2") (pintype "passive"))
      (node (ref "C77") (pin "2") (pinfunction "2_2") (pintype "passive"))
      (node (ref "C78") (pin "2") (pinfunction "2_2") (pintype "passive"))
      (node (ref "C79") (pin "2") (pinfunction "2_2") (pintype "passive"))
      (node (ref "C8") (pin "2") (pinfunction "2_2") (pintype "passive"))
      (node (ref "C80") (pin "2") (pinfunction "2_2") (pintype "passive"))
      (node (ref "C81") (pin "2") (pinfunction "2_2") (pintype "passive"))
      (node (ref "C82") (pin "2") (pinfunction "2_2") (pintype "passive"))
      (node (ref "C83") (pin "2") (pinfunction "2_2") (pintype "passive"))
      (node (ref "C84") (pin "2") (pinfunction "2_2") (pintype "passive"))
      (node (ref "C9") (pin "2") (pinfunction "2_2") (pintype "passive"))
      (node (ref "CN2") (pin "GND") (pinfunction "GND_GND") (pintype "power_in"))
      (node (ref "CN2") (pin "GNDBREAK") (pinfunction "GNDBREAK_GNDBREAK") (pintype "power_in"))
      (node (ref "IC1") (pin "1") (pinfunction "GND_1") (pintype "input"))
      (node (ref "J1") (pin "6") (pinfunction "GND_6") (pintype "power_in"))
      (node (ref "J1") (pin "S1") (pinfunction "S_S1") (pintype "passive"))
      (node (ref "J1") (pin "S2") (pinfunction "S_S2") (pintype "passive"))
      (node (ref "J1") (pin "S3") (pinfunction "S_S3") (pintype "passive"))
      (node (ref "J1") (pin "S4") (pinfunction "S_S4") (pintype "passive"))
      (node (ref "J3") (pin "13") (pinfunction "MS_13") (pintype "passive"))
      (node (ref "J3") (pin "14") (pinfunction "MS_14") (pintype "passive"))
      (node (ref "J3") (pin "21") (pinfunction "MS_21") (pintype "passive"))
      (node (ref "J3") (pin "22") (pinfunction "MS_22") (pintype "passive"))
      (node (ref "J3") (pin "29") (pinfunction "MS_29") (pintype "passive"))
      (node (ref "J3") (pin "3") (pinfunction "MS_3") (pintype "passive"))
      (node (ref "J3") (pin "36") (pinfunction "MS_36") (pintype "passive"))
      (node (ref "J3") (pin "5") (pinfunction "MS_5") (pintype "passive"))
      (node (ref "J3") (pin "6") (pinfunction "MS_6") (pintype "passive"))
      (node (ref "J4") (pin "12") (pinfunction "4_12") (pintype "passive"))
      (node (ref "J4") (pin "15") (pinfunction "1_15") (pintype "passive"))
      (node (ref "J4") (pin "6") (pinfunction "10_6") (pintype "passive"))
      (node (ref "J4") (pin "9") (pinfunction "7_9") (pintype "passive"))
      (node (ref "JP1") (pin "14") (pinfunction "14_14") (pintype "passive"))
      (node (ref "JP1") (pin "20") (pinfunction "20_20") (pintype "passive"))
      (node (ref "JP1") (pin "25") (pinfunction "25_25") (pintype "passive"))
      (node (ref "JP1") (pin "6") (pinfunction "6_6") (pintype "passive"))
      (node (ref "JP1") (pin "9") (pinfunction "9_9") (pintype "passive"))
      (node (ref "JP10") (pin "18") (pinfunction "18_18") (pintype "passive"))
      (node (ref "JP10") (pin "2") (pinfunction "2_2") (pintype "passive"))
      (node (ref "JP5") (pin "3") (pinfunction "3_3") (pintype "passive"))
      (node (ref "JP6") (pin "18") (pinfunction "18_18") (pintype "passive"))
      (node (ref "JP6") (pin "2") (pinfunction "2_2") (pintype "passive"))
      (node (ref "LED1") (pin "C") (pinfunction "C_C") (pintype "passive"))
      (node (ref "LED2") (pin "C") (pinfunction "C_C") (pintype "passive"))
      (node (ref "Q4") (pin "2") (pinfunction "S_2") (pintype "passive"))
      (node (ref "Q5") (pin "2") (pinfunction "S_2") (pintype "passive"))
      (node (ref "R12") (pin "2") (pinfunction "2_2") (pintype "passive"))
      (node (ref "R14") (pin "1") (pinfunction "1_1") (pintype "passive"))
      (node (ref "R15") (pin "1") (pinfunction "1_1") (pintype "passive"))
      (node (ref "R24") (pin "2") (pinfunction "2_2") (pintype "passive"))
      (node (ref "R27") (pin "1") (pinfunction "1_1") (pintype "passive"))
      (node (ref "R28") (pin "2") (pinfunction "2_2") (pintype "passive"))
      (node (ref "R47") (pin "2") (pinfunction "2_2") (pintype "passive"))
      (node (ref "R62") (pin "2") (pinfunction "2_2") (pintype "passive"))
      (node (ref "U$1") (pin "116") (pinfunction "AGND_116") (pintype "bidirectional"))
      (node (ref "U$1") (pin "P$1") (pinfunction "PAD_P$1") (pintype "bidirectional"))
      (node (ref "U$10") (pin "P$1") (pinfunction "VIN-_P$1") (pintype "input"))
      (node (ref "U$10") (pin "P$4") (pinfunction "VOUT-_P$4") (pintype "output"))
      (node (ref "U$11") (pin "P$1") (pinfunction "VIN-_P$1") (pintype "input"))
      (node (ref "U$11") (pin "P$4") (pinfunction "VOUT-_P$4") (pintype "output"))
      (node (ref "U$12") (pin "P$11") (pinfunction "CLOCKSHIELD_P$11") (pintype "bidirectional"))
      (node (ref "U$12") (pin "P$17") (pinfunction "CECGND_P$17") (pintype "bidirectional"))
      (node (ref "U$12") (pin "P$2") (pinfunction "DATA2SHIELD_P$2") (pintype "bidirectional"))
      (node (ref "U$12") (pin "P$5") (pinfunction "DATA1SHIELD_P$5") (pintype "bidirectional"))
      (node (ref "U$12") (pin "P$8") (pinfunction "DATA0SHIELD_P$8") (pintype "bidirectional"))
      (node (ref "U$13") (pin "4") (pinfunction "VSS_4") (pintype "bidirectional"))
      (node (ref "U$14") (pin "2") (pinfunction "GND_2") (pintype "bidirectional"))
      (node (ref "U$15") (pin "5") (pinfunction "5_5") (pintype "input"))
      (node (ref "U$2") (pin "P$1") (pinfunction "GND1_P$1") (pintype "bidirectional"))
      (node (ref "U$2") (pin "P$20") (pinfunction "GND20_P$20") (pintype "bidirectional"))
      (node (ref "U$2") (pin "P$3") (pinfunction "GND3_P$3") (pintype "bidirectional"))
      (node (ref "U$2") (pin "P$31") (pinfunction "GND31_P$31") (pintype "bidirectional"))
      (node (ref "U$2") (pin "P$33") (pinfunction "GND33_P$33") (pintype "bidirectional"))
      (node (ref "U$2") (pin "P$36") (pinfunction "GND36_P$36") (pintype "bidirectional"))
      (node (ref "U$2") (pin "P$41") (pinfunction "UART_RTS_P$41") (pintype "bidirectional"))
      (node (ref "U$3") (pin "10") (pinfunction "G-_10") (pintype "bidirectional"))
      (node (ref "U$3") (pin "11") (pinfunction "Y-_11") (pintype "bidirectional"))
      (node (ref "U$3") (pin "8") (pinfunction "GND_8") (pintype "bidirectional"))
      (node (ref "U$3") (pin "SHIELD1") (pinfunction "SHIELD0_SHIELD1") (pintype "bidirectional"))
      (node (ref "U$3") (pin "SHIELD2") (pinfunction "SHIELD1_SHIELD2") (pintype "bidirectional"))
      (node (ref "U$4") (pin "P$1") (pinfunction "VIN-_P$1") (pintype "input"))
      (node (ref "U$4") (pin "P$4") (pinfunction "VOUT-_P$4") (pintype "output"))
      (node (ref "U$5") (pin "P$1") (pinfunction "PAD_P$1") (pintype "bidirectional"))
      (node (ref "U$6") (pin "2") (pinfunction "VSS_2") (pintype "bidirectional"))
      (node (ref "U$7") (pin "1") (pinfunction "G_1") (pintype "passive"))
      (node (ref "U$8") (pin "6") (pinfunction "GND_6") (pintype "bidirectional"))
      (node (ref "U$8") (pin "8") (pinfunction "A0_8") (pintype "bidirectional"))
      (node (ref "U$9") (pin "2") (pinfunction "GND_2") (pintype "bidirectional"))
      (node (ref "U1") (pin "4") (pinfunction "GND_4") (pintype "power_in"))
      (node (ref "U2") (pin "1") (pinfunction "1~{OE}_1") (pintype "input"))
      (node (ref "U2") (pin "10") (pinfunction "GND_10") (pintype "passive"))
      (node (ref "U2") (pin "19") (pinfunction "2~{OE}_19") (pintype "input"))
      (node (ref "U2") (pin "2") (pinfunction "1A1_2") (pintype "input"))
      (node (ref "U2") (pin "4") (pinfunction "1A2_4") (pintype "input"))
      (node (ref "U3") (pin "1") (pinfunction "1~{OE}_1") (pintype "input"))
      (node (ref "U3") (pin "10") (pinfunction "GND_10") (pintype "passive"))
      (node (ref "U3") (pin "19") (pinfunction "2~{OE}_19") (pintype "input"))
      (node (ref "U3") (pin "2") (pinfunction "1A1_2") (pintype "input"))
      (node (ref "U3") (pin "4") (pinfunction "1A2_4") (pintype "input"))
      (node (ref "U4") (pin "1") (pinfunction "1~{OE}_1") (pintype "input"))
      (node (ref "U4") (pin "10") (pinfunction "GND_10") (pintype "passive"))
      (node (ref "U4") (pin "19") (pinfunction "2~{OE}_19") (pintype "input"))
      (node (ref "U4") (pin "2") (pinfunction "1A1_2") (pintype "input"))
      (node (ref "U4") (pin "4") (pinfunction "1A2_4") (pintype "input"))
      (node (ref "X1") (pin "GND") (pinfunction "GND_GND") (pintype "bidirectional"))
      (node (ref "X2") (pin "10") (pinfunction "10_10") (pintype "passive"))
      (node (ref "X2") (pin "6") (pinfunction "6_6") (pintype "passive"))
      (node (ref "X2") (pin "7") (pinfunction "7_7") (pintype "passive"))
      (node (ref "X2") (pin "8") (pinfunction "8_8") (pintype "passive"))
    )
    (net (code "40") (name "HDMI_5V") (class "Default")
      (node (ref "R60") (pin "2") (pinfunction "2_2") (pintype "passive"))
      (node (ref "R61") (pin "1") (pinfunction "1_1") (pintype "passive"))
      (node (ref "R63") (pin "1") (pinfunction "1_1") (pintype "passive"))
      (node (ref "R64") (pin "1") (pinfunction "1_1") (pintype "passive"))
      (node (ref "R66") (pin "1") (pinfunction "1_1") (pintype "passive"))
      (node (ref "U$12") (pin "P$18") (pinfunction "VCC_P$18") (pintype "bidirectional"))
      (node (ref "U$5") (pin "64") (pinfunction "RXA_5V_64") (pintype "bidirectional"))
    )
    (net (code "41") (name "HDMI_SCL") (class "Default")
      (node (ref "R64") (pin "2") (pinfunction "2_2") (pintype "passive"))
      (node (ref "U$12") (pin "P$15") (pinfunction "SCL_P$15") (pintype "bidirectional"))
      (node (ref "U$5") (pin "62") (pinfunction "DDCA_SCL_62") (pintype "bidirectional"))
    )
    (net (code "42") (name "HDMI_SDA") (class "Default")
      (node (ref "R63") (pin "2") (pinfunction "2_2") (pintype "passive"))
      (node (ref "U$12") (pin "P$16") (pinfunction "SDA_P$16") (pintype "bidirectional"))
      (node (ref "U$5") (pin "63") (pinfunction "DDCA_SDA_63") (pintype "bidirectional"))
    )
    (net (code "43") (name "HOTPLUG") (class "Default")
      (node (ref "Q5") (pin "3") (pinfunction "D_3") (pintype "passive"))
      (node (ref "R60") (pin "1") (pinfunction "1_1") (pintype "passive"))
      (node (ref "U$12") (pin "P$19") (pinfunction "HOTPLUG_P$19") (pintype "bidirectional"))
      (node (ref "U$5") (pin "1") (pinfunction "HPA_A/INT2_1") (pintype "bidirectional"))
    )
    (net (code "44") (name "HP_COM") (class "Default")
      (node (ref "C18") (pin "2") (pinfunction "2_2") (pintype "passive"))
      (node (ref "J2") (pin "RING2") (pinfunction "RING2_RING2") (pintype "bidirectional"))
      (node (ref "R26") (pin "2") (pinfunction "2_2") (pintype "passive"))
      (node (ref "U$1") (pin "125") (pinfunction "HPCOM_125") (pintype "bidirectional"))
    )
    (net (code "45") (name "HP_COMFB") (class "Default")
      (node (ref "R26") (pin "1") (pinfunction "1_1") (pintype "passive"))
      (node (ref "U$1") (pin "124") (pinfunction "HPCOMFB_124") (pintype "bidirectional"))
    )
    (net (code "46") (name "HP_L") (class "Default")
      (node (ref "J2") (pin "TIP") (pinfunction "TIP_TIP") (pintype "bidirectional"))
      (node (ref "U$1") (pin "121") (pinfunction "HPOUTL_121") (pintype "bidirectional"))
    )
    (net (code "47") (name "HP_R") (class "Default")
      (node (ref "J2") (pin "RING1") (pinfunction "RING1_RING1") (pintype "bidirectional"))
      (node (ref "U$1") (pin "120") (pinfunction "HPOUTR_120") (pintype "bidirectional"))
    )
    (net (code "48") (name "I2C0{slash}SCL") (class "Default")
      (node (ref "JP1") (pin "5") (pinfunction "5_5") (pintype "passive"))
      (node (ref "U$1") (pin "45") (pinfunction "PB6/I2C0/SCL_45") (pintype "bidirectional"))
    )
    (net (code "49") (name "I2C0{slash}SDA") (class "Default")
      (node (ref "JP1") (pin "3") (pinfunction "3_3") (pintype "passive"))
      (node (ref "U$1") (pin "46") (pinfunction "PB7/I2C0/SDA_46") (pintype "bidirectional"))
    )
    (net (code "50") (name "I2C1{slash}SCL") (class "Default")
      (node (ref "J4") (pin "3") (pinfunction "13_3") (pintype "passive"))
      (node (ref "JP1") (pin "26") (pinfunction "26_26") (pintype "passive"))
      (node (ref "JP10") (pin "3") (pinfunction "3_3") (pintype "passive"))
      (node (ref "JP6") (pin "3") (pinfunction "3_3") (pintype "passive"))
      (node (ref "R38") (pin "2") (pinfunction "2_2") (pintype "passive"))
      (node (ref "R44") (pin "2") (pinfunction "2_2") (pintype "passive"))
      (node (ref "R65") (pin "2") (pinfunction "2_2") (pintype "passive"))
      (node (ref "U$1") (pin "9") (pinfunction "PE21/UART1/TX_9") (pintype "bidirectional"))
      (node (ref "U$5") (pin "53") (pinfunction "I2C/SCL_53") (pintype "bidirectional"))
      (node (ref "U$8") (pin "10") (pinfunction "SCL_10") (pintype "bidirectional"))
    )
    (net (code "51") (name "I2C1{slash}SDA") (class "Default")
      (node (ref "J4") (pin "2") (pinfunction "14_2") (pintype "passive"))
      (node (ref "JP1") (pin "22") (pinfunction "22_22") (pintype "passive"))
      (node (ref "JP10") (pin "4") (pinfunction "4_4") (pintype "passive"))
      (node (ref "JP6") (pin "4") (pinfunction "4_4") (pintype "passive"))
      (node (ref "R39") (pin "2") (pinfunction "2_2") (pintype "passive"))
      (node (ref "R45") (pin "2") (pinfunction "2_2") (pintype "passive"))
      (node (ref "R67") (pin "1") (pinfunction "1_1") (pintype "passive"))
      (node (ref "U$1") (pin "8") (pinfunction "PE22/UART1/RX_8") (pintype "bidirectional"))
      (node (ref "U$5") (pin "54") (pinfunction "I2C/SDA_54") (pintype "bidirectional"))
      (node (ref "U$8") (pin "9") (pinfunction "SDA_9") (pintype "bidirectional"))
    )
    (net (code "52") (name "KEYADC0") (class "Default")
      (node (ref "C34") (pin "2") (pinfunction "2_2") (pintype "passive"))
      (node (ref "R29") (pin "1") (pinfunction "1_1") (pintype "passive"))
      (node (ref "U$1") (pin "112") (pinfunction "LRADC0_112") (pintype "bidirectional"))
    )
    (net (code "53") (name "LCD_D22") (class "Default")
      (node (ref "J3") (pin "11") (pinfunction "MS_11") (pintype "passive"))
      (node (ref "U$1") (pin "7") (pinfunction "PE23/LCD-D22/_7") (pintype "bidirectional"))
      (node (ref "U4") (pin "15") (pinfunction "2A3_15") (pintype "input"))
    )
    (net (code "54") (name "LCD_D23") (class "Default")
      (node (ref "J3") (pin "12") (pinfunction "MS_12") (pintype "passive"))
      (node (ref "U$1") (pin "6") (pinfunction "PE24/LCD-D23_6") (pintype "bidirectional"))
      (node (ref "U4") (pin "17") (pinfunction "2A4_17") (pintype "input"))
    )
    (net (code "55") (name "LINK_LED") (class "Default")
      (node (ref "R53") (pin "1") (pinfunction "1_1") (pintype "passive"))
      (node (ref "U$1") (pin "77") (pinfunction "EPHY_LINK_LED_77") (pintype "bidirectional"))
    )
    (net (code "56") (name "MCSI-CKN") (class "Default")
      (node (ref "J4") (pin "8") (pinfunction "8_8") (pintype "passive"))
      (node (ref "U$1") (pin "87") (pinfunction "MCSI-CKN_87") (pintype "bidirectional"))
    )
    (net (code "57") (name "MCSI-CKP") (class "Default")
      (node (ref "J4") (pin "7") (pinfunction "9_7") (pintype "passive"))
      (node (ref "U$1") (pin "86") (pinfunction "MCSI-CKP_86") (pintype "bidirectional"))
    )
    (net (code "58") (name "MCSI-D0N") (class "Default")
      (node (ref "J4") (pin "14") (pinfunction "2_14") (pintype "passive"))
      (node (ref "U$1") (pin "82") (pinfunction "MCSI-D0N_82") (pintype "bidirectional"))
    )
    (net (code "59") (name "MCSI-D0P") (class "Default")
      (node (ref "J4") (pin "13") (pinfunction "3_13") (pintype "passive"))
      (node (ref "U$1") (pin "81") (pinfunction "MCSI-D0P_81") (pintype "bidirectional"))
    )
    (net (code "60") (name "MCSI-D1N") (class "Default")
      (node (ref "J4") (pin "11") (pinfunction "5_11") (pintype "passive"))
      (node (ref "U$1") (pin "84") (pinfunction "MCSI-D1N_84") (pintype "bidirectional"))
    )
    (net (code "61") (name "MCSI-D1P") (class "Default")
      (node (ref "J4") (pin "10") (pinfunction "6_10") (pintype "passive"))
      (node (ref "U$1") (pin "83") (pinfunction "MCSI-D1P_83") (pintype "bidirectional"))
    )
    (net (code "62") (name "MICIN1N") (class "Default")
      (node (ref "C28") (pin "1") (pinfunction "1_1") (pintype "passive"))
      (node (ref "U$1") (pin "114") (pinfunction "MICIN1N_114") (pintype "bidirectional"))
    )
    (net (code "63") (name "MICIN1P") (class "Default")
      (node (ref "C27") (pin "1") (pinfunction "1_1") (pintype "passive"))
      (node (ref "U$1") (pin "113") (pinfunction "MICIN1P_113") (pintype "bidirectional"))
    )
    (net (code "64") (name "MIC_HBIAS") (class "Default")
      (node (ref "C17") (pin "1") (pinfunction "1_1") (pintype "passive"))
      (node (ref "R25") (pin "2") (pinfunction "2_2") (pintype "passive"))
      (node (ref "U$1") (pin "119") (pinfunction "HBIAS_119") (pintype "bidirectional"))
    )
    (net (code "65") (name "MIPI-CSI-MCLK{slash}CSI-FIELD") (class "Default")
      (node (ref "J4") (pin "5") (pinfunction "11_5") (pintype "passive"))
      (node (ref "JP1") (pin "15") (pinfunction "15_15") (pintype "passive"))
      (node (ref "U$1") (pin "10") (pinfunction "PE20/CSI-FIELD/CSI-MIPI-M-CLK_10") (pintype "bidirectional"))
    )
    (net (code "66") (name "Net-(ANT2-PadD)") (class "Default")
      (node (ref "ANT2") (pin "D") (pinfunction "D_D") (pintype "bidirectional"))
      (node (ref "C4") (pin "2") (pinfunction "2_2") (pintype "passive"))
    )
    (net (code "67") (name "Net-(C18-Pad1)") (class "Default")
      (node (ref "C18") (pin "1") (pinfunction "1_1") (pintype "passive"))
      (node (ref "R15") (pin "2") (pinfunction "2_2") (pintype "passive"))
    )
    (net (code "68") (name "Net-(C23-Pad2)") (class "Default")
      (node (ref "C23") (pin "2") (pinfunction "2_2") (pintype "passive"))
      (node (ref "C25") (pin "2") (pinfunction "2_2") (pintype "passive"))
      (node (ref "C27") (pin "2") (pinfunction "2_2") (pintype "passive"))
      (node (ref "MIC") (pin "2") (pinfunction "2_2") (pintype "passive"))
      (node (ref "R30") (pin "1") (pinfunction "1_1") (pintype "passive"))
    )
    (net (code "69") (name "Net-(C24-Pad2)") (class "Default")
      (node (ref "C24") (pin "2") (pinfunction "2_2") (pintype "passive"))
      (node (ref "C25") (pin "1") (pinfunction "1_1") (pintype "passive"))
      (node (ref "C28") (pin "2") (pinfunction "2_2") (pintype "passive"))
      (node (ref "MIC") (pin "1") (pinfunction "1_1") (pintype "passive"))
      (node (ref "R28") (pin "1") (pinfunction "1_1") (pintype "passive"))
    )
    (net (code "70") (name "Net-(CN2-PadPWR)") (class "Default")
      (node (ref "CN2") (pin "PWR") (pinfunction "PWR_PWR") (pintype "power_in"))
      (node (ref "F1") (pin "1") (pinfunction "1_1") (pintype "passive"))
    )
    (net (code "71") (name "Net-(J2-PadEARTH)") (class "Default")
      (node (ref "J2") (pin "EARTH") (pinfunction "EARTH_EARTH") (pintype "bidirectional"))
      (node (ref "R25") (pin "1") (pinfunction "1_1") (pintype "passive"))
    )
    (net (code "72") (name "Net-(L1-2)") (class "Default")
      (node (ref "D1") (pin "A") (pinfunction "A_A") (pintype "passive"))
      (node (ref "L1") (pin "P$2") (pinfunction "2_P$2") (pintype "passive"))
      (node (ref "U$9") (pin "1") (pinfunction "SW_1") (pintype "bidirectional"))
    )
    (net (code "73") (name "Net-(LED1-PadA)") (class "Default")
      (node (ref "LED1") (pin "A") (pinfunction "A_A") (pintype "passive"))
      (node (ref "R16") (pin "1") (pinfunction "1_1") (pintype "passive"))
    )
    (net (code "74") (name "Net-(LED2-PadA)") (class "Default")
      (node (ref "LED2") (pin "A") (pinfunction "A_A") (pintype "passive"))
      (node (ref "R17") (pin "1") (pinfunction "1_1") (pintype "passive"))
    )
    (net (code "75") (name "Net-(Q4-D)") (class "Default")
      (node (ref "Q4") (pin "3") (pinfunction "D_3") (pintype "passive"))
      (node (ref "Q5") (pin "1") (pinfunction "G_1") (pintype "passive"))
      (node (ref "R66") (pin "2") (pinfunction "2_2") (pintype "passive"))
    )
    (net (code "76") (name "Net-(U$1A-HPVCCBP)") (class "Default")
      (node (ref "C22") (pin "1") (pinfunction "1_1") (pintype "passive"))
      (node (ref "C29") (pin "2") (pinfunction "2_2") (pintype "passive"))
      (node (ref "U$1") (pin "123") (pinfunction "HPVCCBP_123") (pintype "bidirectional"))
    )
    (net (code "77") (name "Net-(U$1D-RESET)") (class "Default")
      (node (ref "C13") (pin "1") (pinfunction "1_1") (pintype "passive"))
      (node (ref "R11") (pin "1") (pinfunction "1_1") (pintype "passive"))
      (node (ref "U$1") (pin "99") (pinfunction "RESET_99") (pintype "bidirectional"))
    )
    (net (code "78") (name "Net-(U$1D-X24MIN)") (class "Default")
      (node (ref "C12") (pin "2") (pinfunction "2_2") (pintype "passive"))
      (node (ref "Q1") (pin "2") (pinfunction "2_2") (pintype "passive"))
      (node (ref "U$1") (pin "75") (pinfunction "X24MIN_75") (pintype "bidirectional"))
    )
    (net (code "79") (name "Net-(U$1D-X24MOUNT)") (class "Default")
      (node (ref "C11") (pin "2") (pinfunction "2_2") (pintype "passive"))
      (node (ref "Q1") (pin "1") (pinfunction "1_1") (pintype "passive"))
      (node (ref "U$1") (pin "74") (pinfunction "X24MOUNT_74") (pintype "bidirectional"))
    )
    (net (code "80") (name "Net-(U$1D-X32KIN)") (class "Default")
      (node (ref "C8") (pin "1") (pinfunction "1_1") (pintype "passive"))
      (node (ref "Q2") (pin "1") (pinfunction "1_1") (pintype "passive"))
      (node (ref "R3") (pin "2") (pinfunction "2_2") (pintype "passive"))
      (node (ref "U$1") (pin "96") (pinfunction "X32KIN_96") (pintype "bidirectional"))
    )
    (net (code "81") (name "Net-(U$1D-X32KOUT)") (class "Default")
      (node (ref "C10") (pin "1") (pinfunction "1_1") (pintype "passive"))
      (node (ref "Q2") (pin "2") (pinfunction "2_2") (pintype "passive"))
      (node (ref "R3") (pin "1") (pinfunction "1_1") (pintype "passive"))
      (node (ref "U$1") (pin "95") (pinfunction "X32KOUT_95") (pintype "bidirectional"))
    )
    (net (code "82") (name "Net-(U$1E-EPHY_RTX)") (class "Default")
      (node (ref "R24") (pin "1") (pinfunction "1_1") (pintype "passive"))
      (node (ref "U$1") (pin "94") (pinfunction "EPHY_RTX_94") (pintype "bidirectional"))
    )
    (net (code "83") (name "Net-(U$1F-RTC-VIO)") (class "Default")
      (node (ref "C7") (pin "1") (pinfunction "1_1") (pintype "passive"))
      (node (ref "U$1") (pin "97") (pinfunction "RTC-VIO_97") (pintype "bidirectional"))
    )
    (net (code "84") (name "Net-(U$1F-VCC-RTC)") (class "Default")
      (node (ref "JP5") (pin "2") (pinfunction "2_2") (pintype "passive"))
      (node (ref "U$1") (pin "98") (pinfunction "VCC-RTC_98") (pintype "bidirectional"))
    )
    (net (code "85") (name "Net-(U$1G-SZQ)") (class "Default")
      (node (ref "R12") (pin "1") (pinfunction "1_1") (pintype "passive"))
      (node (ref "U$1") (pin "73") (pinfunction "SZQ_73") (pintype "bidirectional"))
    )
    (net (code "86") (name "Net-(U$2-BT_RST)") (class "Default")
      (node (ref "R10") (pin "1") (pinfunction "1_1") (pintype "passive"))
      (node (ref "U$2") (pin "P$34") (pinfunction "BT_RST_P$34") (pintype "bidirectional"))
    )
    (net (code "87") (name "Net-(U$2-UART_CTS)") (class "Default")
      (node (ref "JP7") (pin "3") (pinfunction "3_3") (pintype "passive"))
      (node (ref "U$2") (pin "P$44") (pinfunction "UART_CTS_P$44") (pintype "bidirectional"))
    )
    (net (code "88") (name "Net-(U$2-UART_RXD)") (class "Default")
      (node (ref "JP7") (pin "2") (pinfunction "2_2") (pintype "passive"))
      (node (ref "U$2") (pin "P$43") (pinfunction "UART_RXD_P$43") (pintype "bidirectional"))
    )
    (net (code "89") (name "Net-(U$2-UART_TXD)") (class "Default")
      (node (ref "JP7") (pin "1") (pinfunction "1_1") (pintype "passive"))
      (node (ref "U$2") (pin "P$42") (pinfunction "UART_TXD_P$42") (pintype "bidirectional"))
    )
    (net (code "90") (name "Net-(U$2-VIN_LDO)") (class "Default")
      (node (ref "R19") (pin "1") (pinfunction "1_1") (pintype "passive"))
      (node (ref "U$2") (pin "P$23") (pinfunction "VIN_LDO_P$23") (pintype "bidirectional"))
    )
    (net (code "91") (name "Net-(U$2-WL_BT_ANT)") (class "Default")
      (node (ref "C4") (pin "1") (pinfunction "1_1") (pintype "passive"))
      (node (ref "U$2") (pin "P$2") (pinfunction "WL_BT_ANT_P$2") (pintype "bidirectional"))
    )
    (net (code "92") (name "Net-(U$2-WL_REG)") (class "Default")
      (node (ref "R9") (pin "2") (pinfunction "2_2") (pintype "passive"))
      (node (ref "U$2") (pin "P$12") (pinfunction "WL_REG_P$12") (pintype "bidirectional"))
    )
    (net (code "93") (name "Net-(U$3-G+)") (class "Default")
      (node (ref "R53") (pin "2") (pinfunction "2_2") (pintype "passive"))
      (node (ref "U$3") (pin "9") (pinfunction "G+_9") (pintype "bidirectional"))
    )
    (net (code "94") (name "Net-(U$3-P4)") (class "Default")
      (node (ref "C49") (pin "1") (pinfunction "1_1") (pintype "passive"))
      (node (ref "L2") (pin "2") (pinfunction "2_2") (pintype "passive"))
      (node (ref "R42") (pin "2") (pinfunction "2_2") (pintype "passive"))
      (node (ref "R43") (pin "2") (pinfunction "2_2") (pintype "passive"))
      (node (ref "U$3") (pin "4") (pinfunction "P4_4") (pintype "bidirectional"))
    )
    (net (code "95") (name "Net-(U$3-P5)") (class "Default")
      (node (ref "C48") (pin "1") (pinfunction "1_1") (pintype "passive"))
      (node (ref "R40") (pin "2") (pinfunction "2_2") (pintype "passive"))
      (node (ref "R41") (pin "2") (pinfunction "2_2") (pintype "passive"))
      (node (ref "U$3") (pin "5") (pinfunction "P5_5") (pintype "bidirectional"))
    )
    (net (code "96") (name "Net-(U$3-Y+)") (class "Default")
      (node (ref "R52") (pin "2") (pinfunction "2_2") (pintype "passive"))
      (node (ref "U$3") (pin "12") (pinfunction "Y+_12") (pintype "bidirectional"))
    )
    (net (code "97") (name "Net-(U$4-VOUT+)") (class "Default")
      (node (ref "R69") (pin "1") (pinfunction "1_1") (pintype "passive"))
      (node (ref "U$4") (pin "P$3") (pinfunction "VOUT+_P$3") (pintype "output"))
    )
    (net (code "98") (name "Net-(U$5D-XTALN)") (class "Default")
      (node (ref "C40") (pin "1") (pinfunction "1_1") (pintype "passive"))
      (node (ref "Q3") (pin "2") (pinfunction "2_2") (pintype "passive"))
      (node (ref "R59") (pin "2") (pinfunction "2_2") (pintype "passive"))
      (node (ref "U$5") (pin "59") (pinfunction "XTALN_59") (pintype "bidirectional"))
    )
    (net (code "99") (name "Net-(U$5D-XTALP)") (class "Default")
      (node (ref "C41") (pin "1") (pinfunction "1_1") (pintype "passive"))
      (node (ref "Q3") (pin "1") (pinfunction "1_1") (pintype "passive"))
      (node (ref "R59") (pin "1") (pinfunction "1_1") (pintype "passive"))
      (node (ref "U$5") (pin "58") (pinfunction "XTALP_58") (pintype "bidirectional"))
    )
    (net (code "100") (name "Net-(U$7-D)") (class "Default")
      (node (ref "F1") (pin "2") (pinfunction "2_2") (pintype "passive"))
      (node (ref "U$7") (pin "3") (pinfunction "D_3") (pintype "passive"))
    )
    (net (code "101") (name "Net-(U$10-VOUT+)") (class "Default")
      (node (ref "R70") (pin "1") (pinfunction "1_1") (pintype "passive"))
      (node (ref "U$10") (pin "P$3") (pinfunction "VOUT+_P$3") (pintype "output"))
    )
    (net (code "102") (name "Net-(U$11-VOUT+)") (class "Default")
      (node (ref "R71") (pin "1") (pinfunction "1_1") (pintype "passive"))
      (node (ref "U$11") (pin "P$3") (pinfunction "VOUT+_P$3") (pintype "output"))
    )
    (net (code "103") (name "Net-(U2-1Y3)") (class "Default")
      (node (ref "R4") (pin "2") (pinfunction "2_2") (pintype "passive"))
      (node (ref "U2") (pin "14") (pinfunction "1Y3_14") (pintype "output"))
    )
    (net (code "104") (name "Net-(U2-1Y4)") (class "Default")
      (node (ref "R5") (pin "2") (pinfunction "2_2") (pintype "passive"))
      (node (ref "U2") (pin "12") (pinfunction "1Y4_12") (pintype "output"))
    )
    (net (code "105") (name "Net-(U2-2Y1)") (class "Default")
      (node (ref "R6") (pin "2") (pinfunction "2_2") (pintype "passive"))
      (node (ref "U2") (pin "9") (pinfunction "2Y1_9") (pintype "output"))
    )
    (net (code "106") (name "Net-(U2-2Y2)") (class "Default")
      (node (ref "R7") (pin "2") (pinfunction "2_2") (pintype "passive"))
      (node (ref "U2") (pin "7") (pinfunction "2Y2_7") (pintype "output"))
    )
    (net (code "107") (name "Net-(U2-2Y3)") (class "Default")
      (node (ref "R18") (pin "2") (pinfunction "2_2") (pintype "passive"))
      (node (ref "U2") (pin "5") (pinfunction "2Y3_5") (pintype "output"))
    )
    (net (code "108") (name "Net-(U2-2Y4)") (class "Default")
      (node (ref "R31") (pin "2") (pinfunction "2_2") (pintype "passive"))
      (node (ref "U2") (pin "3") (pinfunction "2Y4_3") (pintype "output"))
    )
    (net (code "109") (name "Net-(U3-1Y3)") (class "Default")
      (node (ref "R33") (pin "2") (pinfunction "2_2") (pintype "passive"))
      (node (ref "U3") (pin "14") (pinfunction "1Y3_14") (pintype "output"))
    )
    (net (code "110") (name "Net-(U3-1Y4)") (class "Default")
      (node (ref "R34") (pin "2") (pinfunction "2_2") (pintype "passive"))
      (node (ref "U3") (pin "12") (pinfunction "1Y4_12") (pintype "output"))
    )
    (net (code "111") (name "Net-(U3-2Y1)") (class "Default")
      (node (ref "R35") (pin "2") (pinfunction "2_2") (pintype "passive"))
      (node (ref "U3") (pin "9") (pinfunction "2Y1_9") (pintype "output"))
    )
    (net (code "112") (name "Net-(U3-2Y2)") (class "Default")
      (node (ref "R37") (pin "2") (pinfunction "2_2") (pintype "passive"))
      (node (ref "U3") (pin "7") (pinfunction "2Y2_7") (pintype "output"))
    )
    (net (code "113") (name "Net-(U3-2Y3)") (class "Default")
      (node (ref "R46") (pin "2") (pinfunction "2_2") (pintype "passive"))
      (node (ref "U3") (pin "5") (pinfunction "2Y3_5") (pintype "output"))
    )
    (net (code "114") (name "Net-(U3-2Y4)") (class "Default")
      (node (ref "R48") (pin "2") (pinfunction "2_2") (pintype "passive"))
      (node (ref "U3") (pin "3") (pinfunction "2Y4_3") (pintype "output"))
    )
    (net (code "115") (name "Net-(U4-1Y3)") (class "Default")
      (node (ref "R49") (pin "2") (pinfunction "2_2") (pintype "passive"))
      (node (ref "U4") (pin "14") (pinfunction "1Y3_14") (pintype "output"))
    )
    (net (code "116") (name "Net-(U4-1Y4)") (class "Default")
      (node (ref "R50") (pin "2") (pinfunction "2_2") (pintype "passive"))
      (node (ref "U4") (pin "12") (pinfunction "1Y4_12") (pintype "output"))
    )
    (net (code "117") (name "Net-(U4-2Y1)") (class "Default")
      (node (ref "R51") (pin "2") (pinfunction "2_2") (pintype "passive"))
      (node (ref "U4") (pin "9") (pinfunction "2Y1_9") (pintype "output"))
    )
    (net (code "118") (name "Net-(U4-2Y2)") (class "Default")
      (node (ref "R54") (pin "2") (pinfunction "2_2") (pintype "passive"))
      (node (ref "U4") (pin "7") (pinfunction "2Y2_7") (pintype "output"))
    )
    (net (code "119") (name "Net-(U4-2Y3)") (class "Default")
      (node (ref "R55") (pin "2") (pinfunction "2_2") (pintype "passive"))
      (node (ref "U4") (pin "5") (pinfunction "2Y3_5") (pintype "output"))
    )
    (net (code "120") (name "Net-(U4-2Y4)") (class "Default")
      (node (ref "R56") (pin "2") (pinfunction "2_2") (pintype "passive"))
      (node (ref "U4") (pin "3") (pinfunction "2Y4_3") (pintype "output"))
    )
    (net (code "121") (name "PB2{slash}ACT_LED") (class "Default")
      (node (ref "JP1") (pin "12") (pinfunction "12_12") (pintype "passive"))
      (node (ref "R17") (pin "2") (pinfunction "2_2") (pintype "passive"))
      (node (ref "U$1") (pin "41") (pinfunction "PB2_41") (pintype "bidirectional"))
    )
    (net (code "122") (name "PB3{slash}HOTPLUG_GPIO") (class "Default")
      (node (ref "J4") (pin "4") (pinfunction "12_4") (pintype "passive"))
      (node (ref "JP1") (pin "7") (pinfunction "7_7") (pintype "passive"))
      (node (ref "R61") (pin "2") (pinfunction "2_2") (pintype "passive"))
      (node (ref "R62") (pin "1") (pinfunction "1_1") (pintype "passive"))
      (node (ref "U$1") (pin "42") (pinfunction "PB3_42") (pintype "bidirectional"))
    )
    (net (code "123") (name "PB4{slash}PWM0") (class "Default")
      (node (ref "JP1") (pin "13") (pinfunction "13_13") (pintype "passive"))
      (node (ref "U$1") (pin "43") (pinfunction "PB4/PWM0_43") (pintype "bidirectional"))
    )
    (net (code "124") (name "PB5{slash}PWM1") (class "Default")
      (node (ref "JP1") (pin "11") (pinfunction "11_11") (pintype "passive"))
      (node (ref "U$1") (pin "44") (pinfunction "PB5/PWM1_44") (pintype "bidirectional"))
    )
    (net (code "125") (name "RXA_0+") (class "Default")
      (node (ref "U$12") (pin "P$7") (pinfunction "DATA0+_P$7") (pintype "bidirectional"))
      (node (ref "U$5") (pin "7") (pinfunction "RXA_0+_7") (pintype "bidirectional"))
    )
    (net (code "126") (name "RXA_0-") (class "Default")
      (node (ref "U$12") (pin "P$9") (pinfunction "DATA0-_P$9") (pintype "bidirectional"))
      (node (ref "U$5") (pin "6") (pinfunction "RXA_0-_6") (pintype "bidirectional"))
    )
    (net (code "127") (name "RXA_1+") (class "Default")
      (node (ref "U$12") (pin "P$4") (pinfunction "DATA1+_P$4") (pintype "bidirectional"))
      (node (ref "U$5") (pin "10") (pinfunction "RXA_1+_10") (pintype "bidirectional"))
    )
    (net (code "128") (name "RXA_1-") (class "Default")
      (node (ref "U$12") (pin "P$6") (pinfunction "DATA1-_P$6") (pintype "bidirectional"))
      (node (ref "U$5") (pin "9") (pinfunction "RXA_1-_9") (pintype "bidirectional"))
    )
    (net (code "129") (name "RXA_2+") (class "Default")
      (node (ref "U$12") (pin "P$1") (pinfunction "DATA2+_P$1") (pintype "bidirectional"))
      (node (ref "U$5") (pin "13") (pinfunction "RXA_2+_13") (pintype "bidirectional"))
    )
    (net (code "130") (name "RXA_2-") (class "Default")
      (node (ref "U$12") (pin "P$3") (pinfunction "DATA2-_P$3") (pintype "bidirectional"))
      (node (ref "U$5") (pin "12") (pinfunction "RXA_2-_12") (pintype "bidirectional"))
    )
    (net (code "131") (name "RXA_CLK+") (class "Default")
      (node (ref "U$12") (pin "P$10") (pinfunction "CLOCK+_P$10") (pintype "bidirectional"))
      (node (ref "U$5") (pin "4") (pinfunction "RXA_C+_4") (pintype "bidirectional"))
    )
    (net (code "132") (name "RXA_CLK-") (class "Default")
      (node (ref "U$12") (pin "P$12") (pinfunction "CLOCK-_P$12") (pintype "bidirectional"))
      (node (ref "U$5") (pin "3") (pinfunction "RXA_C-_3") (pintype "bidirectional"))
    )
    (net (code "133") (name "SDC0{slash}CLK") (class "Default")
      (node (ref "J1") (pin "5") (pinfunction "CLK(SCLK)_5") (pintype "bidirectional"))
      (node (ref "RN2") (pin "5") (pinfunction "2_5") (pintype "passive"))
      (node (ref "U$1") (pin "105") (pinfunction "PF2/SDC0/CLK_105") (pintype "bidirectional"))
    )
    (net (code "134") (name "SDC0{slash}CMD") (class "Default")
      (node (ref "J1") (pin "3") (pinfunction "CMD(DI)_3") (pintype "bidirectional"))
      (node (ref "RN2") (pin "6") (pinfunction "2_6") (pintype "passive"))
      (node (ref "U$1") (pin "103") (pinfunction "PF3/SDC0/CMD_103") (pintype "bidirectional"))
    )
    (net (code "135") (name "SDC0{slash}D0") (class "Default")
      (node (ref "J1") (pin "7") (pinfunction "DAT0(DO)_7") (pintype "bidirectional"))
      (node (ref "R1") (pin "1") (pinfunction "1_1") (pintype "passive"))
      (node (ref "U$1") (pin "106") (pinfunction "PF1/SDC0/D0_106") (pintype "bidirectional"))
    )
    (net (code "136") (name "SDC0{slash}D1") (class "Default")
      (node (ref "J1") (pin "8") (pinfunction "DAT1_8") (pintype "bidirectional"))
      (node (ref "R2") (pin "1") (pinfunction "1_1") (pintype "passive"))
      (node (ref "U$1") (pin "107") (pinfunction "PF0/SDC0/D1_107") (pintype "bidirectional"))
    )
    (net (code "137") (name "SDC0{slash}D2") (class "Default")
      (node (ref "J1") (pin "1") (pinfunction "DAT2_1") (pintype "bidirectional"))
      (node (ref "RN2") (pin "8") (pinfunction "2_8") (pintype "passive"))
      (node (ref "U$1") (pin "101") (pinfunction "PF5/SDC0/D2_101") (pintype "bidirectional"))
    )
    (net (code "138") (name "SDC0{slash}D3") (class "Default")
      (node (ref "J1") (pin "2") (pinfunction "CD/DAT3(~{CS})_2") (pintype "bidirectional"))
      (node (ref "RN2") (pin "7") (pinfunction "2_7") (pintype "passive"))
      (node (ref "U$1") (pin "102") (pinfunction "PF4/SDC0/D3_102") (pintype "bidirectional"))
    )
    (net (code "139") (name "SDC1{slash}CLK") (class "Default")
      (node (ref "U$1") (pin "5") (pinfunction "PG0/SDC1/CLK_5") (pintype "bidirectional"))
      (node (ref "U$2") (pin "P$17") (pinfunction "SDIO_CLK_P$17") (pintype "bidirectional"))
    )
    (net (code "140") (name "SDC1{slash}CMD") (class "Default")
      (node (ref "R36") (pin "2") (pinfunction "2_2") (pintype "passive"))
      (node (ref "U$1") (pin "4") (pinfunction "PG1/SDC1/CMD_4") (pintype "bidirectional"))
      (node (ref "U$2") (pin "P$16") (pinfunction "SDIO_CMD_P$16") (pintype "bidirectional"))
    )
    (net (code "141") (name "SDC1{slash}D0") (class "Default")
      (node (ref "RN1") (pin "8") (pinfunction "2_8") (pintype "passive"))
      (node (ref "U$1") (pin "3") (pinfunction "PG2/SDC1/D0_3") (pintype "bidirectional"))
      (node (ref "U$2") (pin "P$18") (pinfunction "SDIO_D0_P$18") (pintype "bidirectional"))
    )
    (net (code "142") (name "SDC1{slash}D1") (class "Default")
      (node (ref "RN1") (pin "7") (pinfunction "2_7") (pintype "passive"))
      (node (ref "U$1") (pin "2") (pinfunction "PG3/SDC1/D1_2") (pintype "bidirectional"))
      (node (ref "U$2") (pin "P$19") (pinfunction "SDIO_D1_P$19") (pintype "bidirectional"))
    )
    (net (code "143") (name "SDC1{slash}D2") (class "Default")
      (node (ref "RN1") (pin "6") (pinfunction "2_6") (pintype "passive"))
      (node (ref "U$1") (pin "1") (pinfunction "PG4/SDC1/D2_1") (pintype "bidirectional"))
      (node (ref "U$2") (pin "P$14") (pinfunction "SDIO_D2_P$14") (pintype "bidirectional"))
    )
    (net (code "144") (name "SDC1{slash}D3") (class "Default")
      (node (ref "RN1") (pin "5") (pinfunction "2_5") (pintype "passive"))
      (node (ref "U$1") (pin "128") (pinfunction "PG5/SDC1/D3_128") (pintype "bidirectional"))
      (node (ref "U$2") (pin "P$15") (pinfunction "SDIO_D3_P$15") (pintype "bidirectional"))
    )
    (net (code "145") (name "SPD_LED") (class "Default")
      (node (ref "R52") (pin "1") (pinfunction "1_1") (pintype "passive"))
      (node (ref "U$1") (pin "78") (pinfunction "EPHY_SPD_LED_78") (pintype "bidirectional"))
    )
    (net (code "146") (name "SPI1{slash}CS") (class "Default")
      (node (ref "JP1") (pin "24") (pinfunction "24_24") (pintype "passive"))
      (node (ref "R8") (pin "1") (pinfunction "1_1") (pintype "passive"))
      (node (ref "U$1") (pin "54") (pinfunction "PC2/SPI1/CS_54") (pintype "bidirectional"))
      (node (ref "U1") (pin "1") (pinfunction "CS_1") (pintype "bidirectional"))
    )
    (net (code "147") (name "SPI1{slash}MISO") (class "Default")
      (node (ref "JP1") (pin "21") (pinfunction "21_21") (pintype "passive"))
      (node (ref "U$1") (pin "52") (pinfunction "PC0/SPI1/MISO_52") (pintype "bidirectional"))
      (node (ref "U1") (pin "2") (pinfunction "MISO_2") (pintype "bidirectional"))
    )
    (net (code "148") (name "SPI1{slash}MOSI") (class "Default")
      (node (ref "JP1") (pin "19") (pinfunction "19_19") (pintype "passive"))
      (node (ref "U$1") (pin "55") (pinfunction "PC3/SPI1/MOSI_55") (pintype "bidirectional"))
      (node (ref "U1") (pin "5") (pinfunction "MOSI_5") (pintype "bidirectional"))
    )
    (net (code "149") (name "SPI1{slash}SCK") (class "Default")
      (node (ref "JP1") (pin "23") (pinfunction "23_23") (pintype "passive"))
      (node (ref "U$1") (pin "53") (pinfunction "PC1/SPI1/SCK_53") (pintype "bidirectional"))
      (node (ref "U1") (pin "6") (pinfunction "SCK_6") (pintype "bidirectional"))
    )
    (net (code "150") (name "SVREF") (class "Default")
      (node (ref "C14") (pin "1") (pinfunction "1_1") (pintype "passive"))
      (node (ref "C15") (pin "2") (pinfunction "2_2") (pintype "passive"))
      (node (ref "R13") (pin "1") (pinfunction "1_1") (pintype "passive"))
      (node (ref "R14") (pin "2") (pinfunction "2_2") (pintype "passive"))
      (node (ref "U$1") (pin "63") (pinfunction "SVREF1_63") (pintype "bidirectional"))
      (node (ref "U$1") (pin "71") (pinfunction "SVREF0_71") (pintype "bidirectional"))
    )
    (net (code "151") (name "TPX1") (class "Default")
      (node (ref "J3") (pin "37") (pinfunction "MS_37") (pintype "passive"))
      (node (ref "U$8") (pin "2") (pinfunction "XP_2") (pintype "bidirectional"))
    )
    (net (code "152") (name "TPX2") (class "Default")
      (node (ref "J3") (pin "39") (pinfunction "MS_39") (pintype "passive"))
      (node (ref "U$8") (pin "4") (pinfunction "XN_4") (pintype "bidirectional"))
    )
    (net (code "153") (name "TPY1") (class "Default")
      (node (ref "J3") (pin "38") (pinfunction "MS_38") (pintype "passive"))
      (node (ref "U$8") (pin "3") (pinfunction "YP_3") (pintype "bidirectional"))
    )
    (net (code "154") (name "TPY2") (class "Default")
      (node (ref "J3") (pin "40") (pinfunction "MS_40") (pintype "passive"))
      (node (ref "U$8") (pin "5") (pinfunction "YN_5") (pintype "bidirectional"))
    )
    (net (code "155") (name "UART0{slash}RX") (class "Default")
      (node (ref "JP1") (pin "10") (pinfunction "10_10") (pintype "passive"))
      (node (ref "U$1") (pin "49") (pinfunction "PB9/I2C1/SDA_49") (pintype "bidirectional"))
    )
    (net (code "156") (name "UART0{slash}TX") (class "Default")
      (node (ref "JP1") (pin "8") (pinfunction "8_8") (pintype "passive"))
      (node (ref "U$1") (pin "48") (pinfunction "PB8/I2C1/SCL_48") (pintype "bidirectional"))
    )
    (net (code "157") (name "UART2{slash}RX{slash}PB1") (class "Default")
      (node (ref "JP1") (pin "16") (pinfunction "16_16") (pintype "passive"))
      (node (ref "U$1") (pin "40") (pinfunction "PB1/UART2/RX_40") (pintype "bidirectional"))
    )
    (net (code "158") (name "UART2{slash}TX{slash}PB0") (class "Default")
      (node (ref "JP1") (pin "18") (pinfunction "18_18") (pintype "passive"))
      (node (ref "U$1") (pin "39") (pinfunction "PB0/UART2/TX_39") (pintype "bidirectional"))
    )
    (net (code "159") (name "USB_DM") (class "Default")
      (node (ref "U$1") (pin "110") (pinfunction "USB-DM_110") (pintype "bidirectional"))
      (node (ref "U$15") (pin "2") (pinfunction "2_2") (pintype "input"))
      (node (ref "X1") (pin "D-") (pinfunction "D-_D-") (pintype "bidirectional"))
    )
    (net (code "160") (name "USB_DP") (class "Default")
      (node (ref "U$1") (pin "111") (pinfunction "USB-DP_111") (pintype "bidirectional"))
      (node (ref "U$15") (pin "3") (pinfunction "3_3") (pintype "input"))
      (node (ref "X1") (pin "D+") (pinfunction "D+_D+") (pintype "bidirectional"))
    )
    (net (code "161") (name "USB{slash}ID") (class "Default")
      (node (ref "R32") (pin "2") (pinfunction "2_2") (pintype "passive"))
      (node (ref "U$1") (pin "100") (pinfunction "PF6_100") (pintype "bidirectional"))
      (node (ref "U$15") (pin "4") (pinfunction "4_4") (pintype "input"))
    )
    (net (code "162") (name "VCC-PE") (class "Default")
      (node (ref "JP3") (pin "2") (pinfunction "2_2") (pintype "passive"))
      (node (ref "R44") (pin "1") (pinfunction "1_1") (pintype "passive"))
      (node (ref "R45") (pin "1") (pinfunction "1_1") (pintype "passive"))
      (node (ref "U$1") (pin "12") (pinfunction "VCC-PE0_12") (pintype "bidirectional"))
      (node (ref "U$1") (pin "29") (pinfunction "VCC-PE1_29") (pintype "bidirectional"))
    )
    (net (code "163") (name "VGA_B") (class "Default")
      (node (ref "R18") (pin "1") (pinfunction "1_1") (pintype "passive"))
      (node (ref "R31") (pin "1") (pinfunction "1_1") (pintype "passive"))
      (node (ref "R4") (pin "1") (pinfunction "1_1") (pintype "passive"))
      (node (ref "R5") (pin "1") (pinfunction "1_1") (pintype "passive"))
      (node (ref "R6") (pin "1") (pinfunction "1_1") (pintype "passive"))
      (node (ref "R7") (pin "1") (pinfunction "1_1") (pintype "passive"))
      (node (ref "X2") (pin "3") (pinfunction "3_3") (pintype "passive"))
    )
    (net (code "164") (name "VGA_G") (class "Default")
      (node (ref "R33") (pin "1") (pinfunction "1_1") (pintype "passive"))
      (node (ref "R34") (pin "1") (pinfunction "1_1") (pintype "passive"))
      (node (ref "R35") (pin "1") (pinfunction "1_1") (pintype "passive"))
      (node (ref "R37") (pin "1") (pinfunction "1_1") (pintype "passive"))
      (node (ref "R46") (pin "1") (pinfunction "1_1") (pintype "passive"))
      (node (ref "R48") (pin "1") (pinfunction "1_1") (pintype "passive"))
      (node (ref "X2") (pin "2") (pinfunction "2_2") (pintype "passive"))
    )
    (net (code "165") (name "VGA_HSYNC") (class "Default")
      (node (ref "R58") (pin "2") (pinfunction "2_2") (pintype "passive"))
      (node (ref "U6") (pin "3") (pinfunction "D_3") (pintype "passive"))
      (node (ref "X2") (pin "13") (pinfunction "13_13") (pintype "passive"))
    )
    (net (code "166") (name "VGA_R") (class "Default")
      (node (ref "R49") (pin "1") (pinfunction "1_1") (pintype "passive"))
      (node (ref "R50") (pin "1") (pinfunction "1_1") (pintype "passive"))
      (node (ref "R51") (pin "1") (pinfunction "1_1") (pintype "passive"))
      (node (ref "R54") (pin "1") (pinfunction "1_1") (pintype "passive"))
      (node (ref "R55") (pin "1") (pinfunction "1_1") (pintype "passive"))
      (node (ref "R56") (pin "1") (pinfunction "1_1") (pintype "passive"))
      (node (ref "X2") (pin "1") (pinfunction "1_1") (pintype "passive"))
    )
    (net (code "167") (name "VGA_VSYNC") (class "Default")
      (node (ref "R57") (pin "2") (pinfunction "2_2") (pintype "passive"))
      (node (ref "U5") (pin "3") (pinfunction "D_3") (pintype "passive"))
      (node (ref "X2") (pin "14") (pinfunction "14_14") (pintype "passive"))
    )
    (net (code "168") (name "VLED+") (class "Default")
      (node (ref "C74") (pin "1") (pinfunction "1_1") (pintype "passive"))
      (node (ref "C75") (pin "1") (pinfunction "1_1") (pintype "passive"))
      (node (ref "D1") (pin "C") (pinfunction "C_C") (pintype "passive"))
      (node (ref "J3") (pin "2") (pinfunction "MS_2") (pintype "passive"))
      (node (ref "U$9") (pin "5") (pinfunction "OV_5") (pintype "bidirectional"))
    )
    (net (code "169") (name "VLED-") (class "Default")
      (node (ref "J3") (pin "1") (pinfunction "MSV_1") (pintype "passive"))
      (node (ref "R47") (pin "1") (pinfunction "1_1") (pintype "passive"))
      (node (ref "U$9") (pin "3") (pinfunction "FB_3") (pintype "bidirectional"))
    )
    (net (code "170") (name "VRA1") (class "Default")
      (node (ref "C21") (pin "2") (pinfunction "2_2") (pintype "passive"))
      (node (ref "U$1") (pin "117") (pinfunction "VRA1_117") (pintype "bidirectional"))
    )
    (net (code "171") (name "VRA2") (class "Default")
      (node (ref "C20") (pin "2") (pinfunction "2_2") (pintype "passive"))
      (node (ref "R27") (pin "2") (pinfunction "2_2") (pintype "passive"))
      (node (ref "U$1") (pin "118") (pinfunction "VRA2_118") (pintype "bidirectional"))
    )
    (net (code "172") (name "WL_H_WK") (class "Default")
      (node (ref "U$2") (pin "P$13") (pinfunction "WL_H_WK_P$13") (pintype "bidirectional"))
    )
    (net (code "173") (name "unconnected-(J3AC-MS-Pad35)") (class "Default")
      (node (ref "J3") (pin "35") (pinfunction "MS_35") (pintype "passive"))
    )
    (net (code "174") (name "unconnected-(U$2-BTXTALOUT-PadP$38)") (class "Default")
      (node (ref "U$2") (pin "P$38") (pinfunction "BTXTALOUT_P$38") (pintype "bidirectional"))
    )
    (net (code "175") (name "unconnected-(U$2-BT_XTAL_IN-PadP$37)") (class "Default")
      (node (ref "U$2") (pin "P$37") (pinfunction "BT_XTAL_IN_P$37") (pintype "bidirectional"))
    )
    (net (code "176") (name "unconnected-(U$2-LPO-PadP$24)") (class "Default")
      (node (ref "U$2") (pin "P$24") (pinfunction "LPO_P$24") (pintype "bidirectional"))
    )
    (net (code "177") (name "unconnected-(U$2-NC4-PadP$4)") (class "Default")
      (node (ref "U$2") (pin "P$4") (pinfunction "NC4_P$4") (pintype "bidirectional"))
    )
    (net (code "178") (name "unconnected-(U$2-NC5-PadP$5)") (class "Default")
      (node (ref "U$2") (pin "P$5") (pinfunction "NC5_P$5") (pintype "bidirectional"))
    )
    (net (code "179") (name "unconnected-(U$2-NC8-PadP$8)") (class "Default")
      (node (ref "U$2") (pin "P$8") (pinfunction "NC8_P$8") (pintype "bidirectional"))
    )
    (net (code "180") (name "unconnected-(U$2-NC32-PadP$32)") (class "Default")
      (node (ref "U$2") (pin "P$32") (pinfunction "NC32_P$32") (pintype "bidirectional"))
    )
    (net (code "181") (name "unconnected-(U$2-NC35-PadP$35)") (class "Default")
      (node (ref "U$2") (pin "P$35") (pinfunction "NC35_P$35") (pintype "bidirectional"))
    )
    (net (code "182") (name "unconnected-(U$2-NC39-PadP$39)") (class "Default")
      (node (ref "U$2") (pin "P$39") (pinfunction "NC39_P$39") (pintype "bidirectional"))
    )
    (net (code "183") (name "unconnected-(U$2-NC40-PadP$40)") (class "Default")
      (node (ref "U$2") (pin "P$40") (pinfunction "NC40_P$40") (pintype "bidirectional"))
    )
    (net (code "184") (name "unconnected-(U$2-PCM_CLK-PadP$26)") (class "Default")
      (node (ref "U$2") (pin "P$26") (pinfunction "PCM_CLK_P$26") (pintype "bidirectional"))
    )
    (net (code "185") (name "unconnected-(U$2-PCM_IN-PadP$27)") (class "Default")
      (node (ref "U$2") (pin "P$27") (pinfunction "PCM_IN_P$27") (pintype "bidirectional"))
    )
    (net (code "186") (name "unconnected-(U$2-PCM_OUT-PadP$25)") (class "Default")
      (node (ref "U$2") (pin "P$25") (pinfunction "PCM_OUT_P$25") (pintype "bidirectional"))
    )
    (net (code "187") (name "unconnected-(U$2-PCM_SYNC-PadP$28)") (class "Default")
      (node (ref "U$2") (pin "P$28") (pinfunction "PCM_SYNC_P$28") (pintype "bidirectional"))
    )
    (net (code "188") (name "unconnected-(U$2-TCXO_IN-PadP$30)") (class "Default")
      (node (ref "U$2") (pin "P$30") (pinfunction "TCXO_IN_P$30") (pintype "bidirectional"))
    )
    (net (code "189") (name "unconnected-(U$2-VDD_TXCO-PadP$29)") (class "Default")
      (node (ref "U$2") (pin "P$29") (pinfunction "VDD_TXCO_P$29") (pintype "bidirectional"))
    )
    (net (code "190") (name "unconnected-(U$2-VIN_LDO_OUT-PadP$21)") (class "Default")
      (node (ref "U$2") (pin "P$21") (pinfunction "VIN_LDO_OUT_P$21") (pintype "bidirectional"))
    )
    (net (code "191") (name "unconnected-(U$2-XTAL_WL_IN-PadP$10)") (class "Default")
      (node (ref "U$2") (pin "P$10") (pinfunction "XTAL_WL_IN_P$10") (pintype "bidirectional"))
    )
    (net (code "192") (name "unconnected-(U$2-XTAL_WL_OUT-PadP$11)") (class "Default")
      (node (ref "U$2") (pin "P$11") (pinfunction "XTAL_WL_OUT_P$11") (pintype "bidirectional"))
    )
    (net (code "193") (name "unconnected-(U$3-NC-Pad7)") (class "Default")
      (node (ref "U$3") (pin "7") (pinfunction "NC_7") (pintype "bidirectional"))
    )
    (net (code "194") (name "unconnected-(U$5A-P16-Pad22)") (class "Default")
      (node (ref "U$5") (pin "22") (pinfunction "P16_22") (pintype "bidirectional"))
    )
    (net (code "195") (name "unconnected-(U$5A-P17-Pad21)") (class "Default")
      (node (ref "U$5") (pin "21") (pinfunction "P17_21") (pintype "bidirectional"))
    )
    (net (code "196") (name "unconnected-(U$5A-P18-Pad20)") (class "Default")
      (node (ref "U$5") (pin "20") (pinfunction "P18_20") (pintype "bidirectional"))
    )
    (net (code "197") (name "unconnected-(U$5A-P19-Pad19)") (class "Default")
      (node (ref "U$5") (pin "19") (pinfunction "P19_19") (pintype "bidirectional"))
    )
    (net (code "198") (name "unconnected-(U$5A-P20-Pad18)") (class "Default")
      (node (ref "U$5") (pin "18") (pinfunction "P20_18") (pintype "bidirectional"))
    )
    (net (code "199") (name "unconnected-(U$5A-P21-Pad17)") (class "Default")
      (node (ref "U$5") (pin "17") (pinfunction "P21_17") (pintype "bidirectional"))
    )
    (net (code "200") (name "unconnected-(U$5A-P22-Pad16)") (class "Default")
      (node (ref "U$5") (pin "16") (pinfunction "P22_16") (pintype "bidirectional"))
    )
    (net (code "201") (name "unconnected-(U$5A-P23-Pad15)") (class "Default")
      (node (ref "U$5") (pin "15") (pinfunction "P23_15") (pintype "bidirectional"))
    )
    (net (code "202") (name "unconnected-(U$5C-AP-Pad48)") (class "Default")
      (node (ref "U$5") (pin "48") (pinfunction "AP_48") (pintype "bidirectional"))
    )
    (net (code "203") (name "unconnected-(U$5C-LRCLK-Pad50)") (class "Default")
      (node (ref "U$5") (pin "50") (pinfunction "LRCLK_50") (pintype "bidirectional"))
    )
    (net (code "204") (name "unconnected-(U$5C-MCLK{slash}INT2-Pad51)") (class "Default")
      (node (ref "U$5") (pin "51") (pinfunction "MCLK/INT2_51") (pintype "bidirectional"))
    )
    (net (code "205") (name "unconnected-(U$5C-SCLK{slash}INT2-Pad49)") (class "Default")
      (node (ref "U$5") (pin "49") (pinfunction "SCLK/INT2_49") (pintype "bidirectional"))
    )
    (net (code "206") (name "unconnected-(U$8-PENIRQ-Pad7)") (class "Default")
      (node (ref "U$8") (pin "7") (pinfunction "PENIRQ_7") (pintype "bidirectional"))
    )
    (net (code "207") (name "unconnected-(U$12-UTIL-PadP$14)") (class "Default")
      (node (ref "U$12") (pin "P$14") (pinfunction "UTIL_P$14") (pintype "bidirectional"))
    )
    (net (code "208") (name "unconnected-(U$13-NC1-Pad2)") (class "Default")
      (node (ref "U$13") (pin "2") (pinfunction "NC1_2") (pintype "bidirectional"))
    )
    (net (code "209") (name "unconnected-(U$13-NC2-Pad6)") (class "Default")
      (node (ref "U$13") (pin "6") (pinfunction "NC2_6") (pintype "bidirectional"))
    )
    (net (code "210") (name "unconnected-(U$14-NC-Pad4)") (class "Default")
      (node (ref "U$14") (pin "4") (pinfunction "NC_4") (pintype "bidirectional"))
    )
    (net (code "211") (name "unconnected-(U$15A-S1-PadM1)") (class "Default")
      (node (ref "U$15") (pin "M1") (pinfunction "S1_M1") (pintype "passive"))
    )
    (net (code "212") (name "unconnected-(U$15A-S2-PadM2)") (class "Default")
      (node (ref "U$15") (pin "M2") (pinfunction "S2_M2") (pintype "passive"))
    )
    (net (code "213") (name "unconnected-(U$15A-S3-PadM3)") (class "Default")
      (node (ref "U$15") (pin "M3") (pinfunction "S3_M3") (pintype "passive"))
    )
    (net (code "214") (name "unconnected-(U$15A-S4-PadM4)") (class "Default")
      (node (ref "U$15") (pin "M4") (pinfunction "S4_M4") (pintype "passive"))
    )
    (net (code "215") (name "unconnected-(U2-1Y1-Pad18)") (class "Default")
      (node (ref "U2") (pin "18") (pinfunction "1Y1_18") (pintype "output"))
    )
    (net (code "216") (name "unconnected-(U2-1Y2-Pad16)") (class "Default")
      (node (ref "U2") (pin "16") (pinfunction "1Y2_16") (pintype "output"))
    )
    (net (code "217") (name "unconnected-(U3-1Y1-Pad18)") (class "Default")
      (node (ref "U3") (pin "18") (pinfunction "1Y1_18") (pintype "output"))
    )
    (net (code "218") (name "unconnected-(U3-1Y2-Pad16)") (class "Default")
      (node (ref "U3") (pin "16") (pinfunction "1Y2_16") (pintype "output"))
    )
    (net (code "219") (name "unconnected-(U4-1Y1-Pad18)") (class "Default")
      (node (ref "U4") (pin "18") (pinfunction "1Y1_18") (pintype "output"))
    )
    (net (code "220") (name "unconnected-(U4-1Y2-Pad16)") (class "Default")
      (node (ref "U4") (pin "16") (pinfunction "1Y2_16") (pintype "output"))
    )
    (net (code "221") (name "unconnected-(X2-Pad4)") (class "Default")
      (node (ref "X2") (pin "4") (pinfunction "4_4") (pintype "passive"))
    )
    (net (code "222") (name "unconnected-(X2-Pad5)") (class "Default")
      (node (ref "X2") (pin "5") (pinfunction "5_5") (pintype "passive"))
    )
    (net (code "223") (name "unconnected-(X2-Pad9)") (class "Default")
      (node (ref "X2") (pin "9") (pinfunction "9_9") (pintype "passive"))
    )
    (net (code "224") (name "unconnected-(X2-Pad11)") (class "Default")
      (node (ref "X2") (pin "11") (pinfunction "11_11") (pintype "passive"))
    )
    (net (code "225") (name "unconnected-(X2-Pad12)") (class "Default")
      (node (ref "X2") (pin "12") (pinfunction "12_12") (pintype "passive"))
    )
    (net (code "226") (name "unconnected-(X2-Pad15)") (class "Default")
      (node (ref "X2") (pin "15") (pinfunction "15_15") (pintype "passive"))
    )
  )
)
